# ELC102_-_Score_Board_-_Red_Digits.net
KiCad netlist of a schematic drawn in Altium Designer
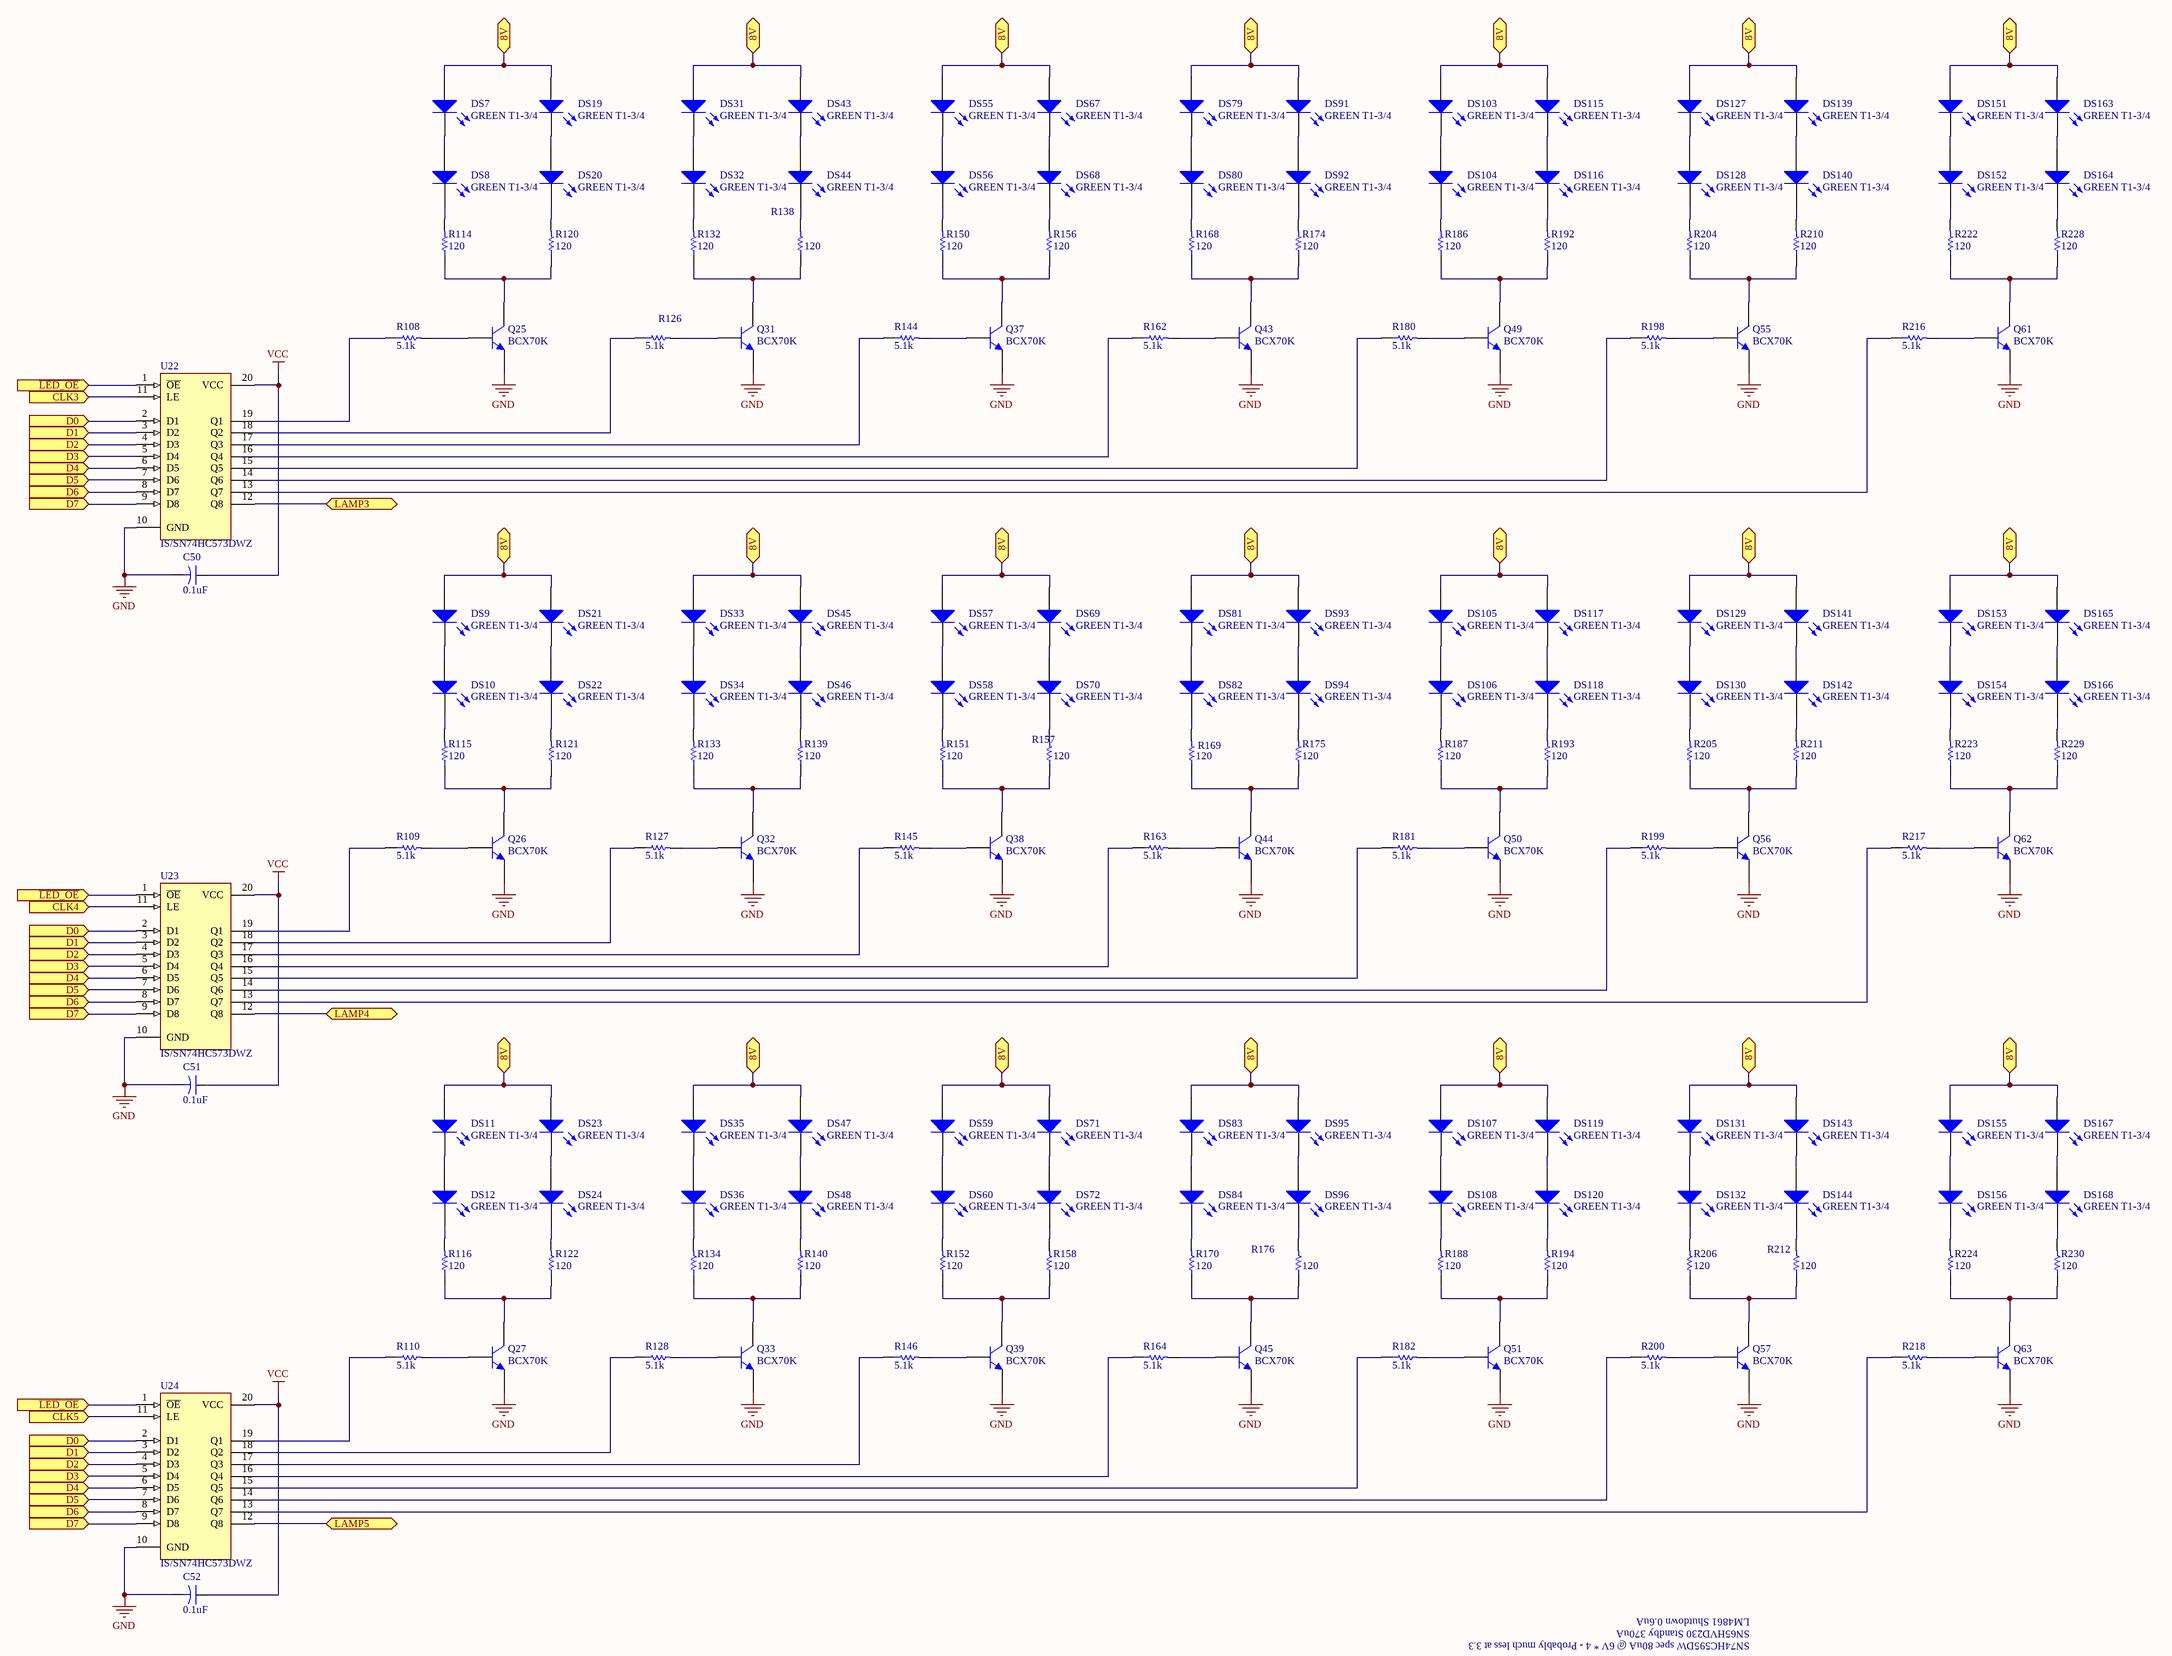
[diagram p0: ELC102 - Score Board - Red Digits.SchDoc]

(export (version "E")
  (design (tool "Eeschema 10.0.6"))
  (components
    (comp (ref "C50")
      (value "0.1uF")
      (footprint "C0805")
      (description "Kemet .1uF 0805")
      (fields
        (field (name "MANUFACTURER") "Kemet")
        (field (name "MANUFACTURER PART NUMBER") "C0805C104K5RACTU")
        (field (name "SOURCE") "Digikey")
      )
      (libsource (lib "ScoreBoard") (part "CS/C0805C104K5RACK"))
    )
    (comp (ref "C51")
      (value "0.1uF")
      (footprint "C0805")
      (description "Kemet .1uF 0805")
      (fields
        (field (name "MANUFACTURER") "Kemet")
        (field (name "MANUFACTURER PART NUMBER") "C0805C104K5RACTU")
        (field (name "SOURCE") "Digikey")
      )
      (libsource (lib "ScoreBoard") (part "CS/C0805C104K5RACK"))
    )
    (comp (ref "C52")
      (value "0.1uF")
      (footprint "C0805")
      (description "Kemet .1uF 0805")
      (fields
        (field (name "MANUFACTURER") "Kemet")
        (field (name "MANUFACTURER PART NUMBER") "C0805C104K5RACTU")
        (field (name "SOURCE") "Digikey")
      )
      (libsource (lib "ScoreBoard") (part "CS/C0805C104K5RACK"))
    )
    (comp (ref "DS7")
      (value "GREEN T1-3/4")
      (footprint "LED T1-3/4 Flush")
      (description "Optek LED Green/Clear High Brightness T1-3/4")
      (fields
        (field (name "MANUFACTURER") "OPTEK")
        (field (name "MANUFACTURER PART NUMBER") "OVLFG3C7")
        (field (name "SOURCE") "Digikey")
      )
      (libsource (lib "ScoreBoard") (part "LGCOVLFG3C7Z"))
    )
    (comp (ref "DS8")
      (value "GREEN T1-3/4")
      (footprint "LED T1-3/4 Flush")
      (description "Optek LED Green/Clear High Brightness T1-3/4")
      (fields
        (field (name "MANUFACTURER") "OPTEK")
        (field (name "MANUFACTURER PART NUMBER") "OVLFG3C7")
        (field (name "SOURCE") "Digikey")
      )
      (libsource (lib "ScoreBoard") (part "LGCOVLFG3C7Z"))
    )
    (comp (ref "DS9")
      (value "GREEN T1-3/4")
      (footprint "LED T1-3/4 Flush")
      (description "Optek LED Green/Clear High Brightness T1-3/4")
      (fields
        (field (name "MANUFACTURER") "OPTEK")
        (field (name "MANUFACTURER PART NUMBER") "OVLFG3C7")
        (field (name "SOURCE") "Digikey")
      )
      (libsource (lib "ScoreBoard") (part "LGCOVLFG3C7Z"))
    )
    (comp (ref "DS10")
      (value "GREEN T1-3/4")
      (footprint "LED T1-3/4 Flush")
      (description "Optek LED Green/Clear High Brightness T1-3/4")
      (fields
        (field (name "MANUFACTURER") "OPTEK")
        (field (name "MANUFACTURER PART NUMBER") "OVLFG3C7")
        (field (name "SOURCE") "Digikey")
      )
      (libsource (lib "ScoreBoard") (part "LGCOVLFG3C7Z"))
    )
    (comp (ref "DS11")
      (value "GREEN T1-3/4")
      (footprint "LED T1-3/4 Flush")
      (description "Optek LED Green/Clear High Brightness T1-3/4")
      (fields
        (field (name "MANUFACTURER") "OPTEK")
        (field (name "MANUFACTURER PART NUMBER") "OVLFG3C7")
        (field (name "SOURCE") "Digikey")
      )
      (libsource (lib "ScoreBoard") (part "LGCOVLFG3C7Z"))
    )
    (comp (ref "DS12")
      (value "GREEN T1-3/4")
      (footprint "LED T1-3/4 Flush")
      (description "Optek LED Green/Clear High Brightness T1-3/4")
      (fields
        (field (name "MANUFACTURER") "OPTEK")
        (field (name "MANUFACTURER PART NUMBER") "OVLFG3C7")
        (field (name "SOURCE") "Digikey")
      )
      (libsource (lib "ScoreBoard") (part "LGCOVLFG3C7Z"))
    )
    (comp (ref "DS19")
      (value "GREEN T1-3/4")
      (footprint "LED T1-3/4 Flush")
      (description "Optek LED Green/Clear High Brightness T1-3/4")
      (fields
        (field (name "MANUFACTURER") "OPTEK")
        (field (name "MANUFACTURER PART NUMBER") "OVLFG3C7")
        (field (name "SOURCE") "Digikey")
      )
      (libsource (lib "ScoreBoard") (part "LGCOVLFG3C7Z"))
    )
    (comp (ref "DS20")
      (value "GREEN T1-3/4")
      (footprint "LED T1-3/4 Flush")
      (description "Optek LED Green/Clear High Brightness T1-3/4")
      (fields
        (field (name "MANUFACTURER") "OPTEK")
        (field (name "MANUFACTURER PART NUMBER") "OVLFG3C7")
        (field (name "SOURCE") "Digikey")
      )
      (libsource (lib "ScoreBoard") (part "LGCOVLFG3C7Z"))
    )
    (comp (ref "DS21")
      (value "GREEN T1-3/4")
      (footprint "LED T1-3/4 Flush")
      (description "Optek LED Green/Clear High Brightness T1-3/4")
      (fields
        (field (name "MANUFACTURER") "OPTEK")
        (field (name "MANUFACTURER PART NUMBER") "OVLFG3C7")
        (field (name "SOURCE") "Digikey")
      )
      (libsource (lib "ScoreBoard") (part "LGCOVLFG3C7Z"))
    )
    (comp (ref "DS22")
      (value "GREEN T1-3/4")
      (footprint "LED T1-3/4 Flush")
      (description "Optek LED Green/Clear High Brightness T1-3/4")
      (fields
        (field (name "MANUFACTURER") "OPTEK")
        (field (name "MANUFACTURER PART NUMBER") "OVLFG3C7")
        (field (name "SOURCE") "Digikey")
      )
      (libsource (lib "ScoreBoard") (part "LGCOVLFG3C7Z"))
    )
    (comp (ref "DS23")
      (value "GREEN T1-3/4")
      (footprint "LED T1-3/4 Flush")
      (description "Optek LED Green/Clear High Brightness T1-3/4")
      (fields
        (field (name "MANUFACTURER") "OPTEK")
        (field (name "MANUFACTURER PART NUMBER") "OVLFG3C7")
        (field (name "SOURCE") "Digikey")
      )
      (libsource (lib "ScoreBoard") (part "LGCOVLFG3C7Z"))
    )
    (comp (ref "DS24")
      (value "GREEN T1-3/4")
      (footprint "LED T1-3/4 Flush")
      (description "Optek LED Green/Clear High Brightness T1-3/4")
      (fields
        (field (name "MANUFACTURER") "OPTEK")
        (field (name "MANUFACTURER PART NUMBER") "OVLFG3C7")
        (field (name "SOURCE") "Digikey")
      )
      (libsource (lib "ScoreBoard") (part "LGCOVLFG3C7Z"))
    )
    (comp (ref "DS31")
      (value "GREEN T1-3/4")
      (footprint "LED T1-3/4 Flush")
      (description "Optek LED Green/Clear High Brightness T1-3/4")
      (fields
        (field (name "MANUFACTURER") "OPTEK")
        (field (name "MANUFACTURER PART NUMBER") "OVLFG3C7")
        (field (name "SOURCE") "Digikey")
      )
      (libsource (lib "ScoreBoard") (part "LGCOVLFG3C7Z"))
    )
    (comp (ref "DS32")
      (value "GREEN T1-3/4")
      (footprint "LED T1-3/4 Flush")
      (description "Optek LED Green/Clear High Brightness T1-3/4")
      (fields
        (field (name "MANUFACTURER") "OPTEK")
        (field (name "MANUFACTURER PART NUMBER") "OVLFG3C7")
        (field (name "SOURCE") "Digikey")
      )
      (libsource (lib "ScoreBoard") (part "LGCOVLFG3C7Z"))
    )
    (comp (ref "DS33")
      (value "GREEN T1-3/4")
      (footprint "LED T1-3/4 Flush")
      (description "Optek LED Green/Clear High Brightness T1-3/4")
      (fields
        (field (name "MANUFACTURER") "OPTEK")
        (field (name "MANUFACTURER PART NUMBER") "OVLFG3C7")
        (field (name "SOURCE") "Digikey")
      )
      (libsource (lib "ScoreBoard") (part "LGCOVLFG3C7Z"))
    )
    (comp (ref "DS34")
      (value "GREEN T1-3/4")
      (footprint "LED T1-3/4 Flush")
      (description "Optek LED Green/Clear High Brightness T1-3/4")
      (fields
        (field (name "MANUFACTURER") "OPTEK")
        (field (name "MANUFACTURER PART NUMBER") "OVLFG3C7")
        (field (name "SOURCE") "Digikey")
      )
      (libsource (lib "ScoreBoard") (part "LGCOVLFG3C7Z"))
    )
    (comp (ref "DS35")
      (value "GREEN T1-3/4")
      (footprint "LED T1-3/4 Flush")
      (description "Optek LED Green/Clear High Brightness T1-3/4")
      (fields
        (field (name "MANUFACTURER") "OPTEK")
        (field (name "MANUFACTURER PART NUMBER") "OVLFG3C7")
        (field (name "SOURCE") "Digikey")
      )
      (libsource (lib "ScoreBoard") (part "LGCOVLFG3C7Z"))
    )
    (comp (ref "DS36")
      (value "GREEN T1-3/4")
      (footprint "LED T1-3/4 Flush")
      (description "Optek LED Green/Clear High Brightness T1-3/4")
      (fields
        (field (name "MANUFACTURER") "OPTEK")
        (field (name "MANUFACTURER PART NUMBER") "OVLFG3C7")
        (field (name "SOURCE") "Digikey")
      )
      (libsource (lib "ScoreBoard") (part "LGCOVLFG3C7Z"))
    )
    (comp (ref "DS43")
      (value "GREEN T1-3/4")
      (footprint "LED T1-3/4 Flush")
      (description "Optek LED Green/Clear High Brightness T1-3/4")
      (fields
        (field (name "MANUFACTURER") "OPTEK")
        (field (name "MANUFACTURER PART NUMBER") "OVLFG3C7")
        (field (name "SOURCE") "Digikey")
      )
      (libsource (lib "ScoreBoard") (part "LGCOVLFG3C7Z"))
    )
    (comp (ref "DS44")
      (value "GREEN T1-3/4")
      (footprint "LED T1-3/4 Flush")
      (description "Optek LED Green/Clear High Brightness T1-3/4")
      (fields
        (field (name "MANUFACTURER") "OPTEK")
        (field (name "MANUFACTURER PART NUMBER") "OVLFG3C7")
        (field (name "SOURCE") "Digikey")
      )
      (libsource (lib "ScoreBoard") (part "LGCOVLFG3C7Z"))
    )
    (comp (ref "DS45")
      (value "GREEN T1-3/4")
      (footprint "LED T1-3/4 Flush")
      (description "Optek LED Green/Clear High Brightness T1-3/4")
      (fields
        (field (name "MANUFACTURER") "OPTEK")
        (field (name "MANUFACTURER PART NUMBER") "OVLFG3C7")
        (field (name "SOURCE") "Digikey")
      )
      (libsource (lib "ScoreBoard") (part "LGCOVLFG3C7Z"))
    )
    (comp (ref "DS46")
      (value "GREEN T1-3/4")
      (footprint "LED T1-3/4 Flush")
      (description "Optek LED Green/Clear High Brightness T1-3/4")
      (fields
        (field (name "MANUFACTURER") "OPTEK")
        (field (name "MANUFACTURER PART NUMBER") "OVLFG3C7")
        (field (name "SOURCE") "Digikey")
      )
      (libsource (lib "ScoreBoard") (part "LGCOVLFG3C7Z"))
    )
    (comp (ref "DS47")
      (value "GREEN T1-3/4")
      (footprint "LED T1-3/4 Flush")
      (description "Optek LED Green/Clear High Brightness T1-3/4")
      (fields
        (field (name "MANUFACTURER") "OPTEK")
        (field (name "MANUFACTURER PART NUMBER") "OVLFG3C7")
        (field (name "SOURCE") "Digikey")
      )
      (libsource (lib "ScoreBoard") (part "LGCOVLFG3C7Z"))
    )
    (comp (ref "DS48")
      (value "GREEN T1-3/4")
      (footprint "LED T1-3/4 Flush")
      (description "Optek LED Green/Clear High Brightness T1-3/4")
      (fields
        (field (name "MANUFACTURER") "OPTEK")
        (field (name "MANUFACTURER PART NUMBER") "OVLFG3C7")
        (field (name "SOURCE") "Digikey")
      )
      (libsource (lib "ScoreBoard") (part "LGCOVLFG3C7Z"))
    )
    (comp (ref "DS55")
      (value "GREEN T1-3/4")
      (footprint "LED T1-3/4 Flush")
      (description "Optek LED Green/Clear High Brightness T1-3/4")
      (fields
        (field (name "MANUFACTURER") "OPTEK")
        (field (name "MANUFACTURER PART NUMBER") "OVLFG3C7")
        (field (name "SOURCE") "Digikey")
      )
      (libsource (lib "ScoreBoard") (part "LGCOVLFG3C7Z"))
    )
    (comp (ref "DS56")
      (value "GREEN T1-3/4")
      (footprint "LED T1-3/4 Flush")
      (description "Optek LED Green/Clear High Brightness T1-3/4")
      (fields
        (field (name "MANUFACTURER") "OPTEK")
        (field (name "MANUFACTURER PART NUMBER") "OVLFG3C7")
        (field (name "SOURCE") "Digikey")
      )
      (libsource (lib "ScoreBoard") (part "LGCOVLFG3C7Z"))
    )
    (comp (ref "DS57")
      (value "GREEN T1-3/4")
      (footprint "LED T1-3/4 Flush")
      (description "Optek LED Green/Clear High Brightness T1-3/4")
      (fields
        (field (name "MANUFACTURER") "OPTEK")
        (field (name "MANUFACTURER PART NUMBER") "OVLFG3C7")
        (field (name "SOURCE") "Digikey")
      )
      (libsource (lib "ScoreBoard") (part "LGCOVLFG3C7Z"))
    )
    (comp (ref "DS58")
      (value "GREEN T1-3/4")
      (footprint "LED T1-3/4 Flush")
      (description "Optek LED Green/Clear High Brightness T1-3/4")
      (fields
        (field (name "MANUFACTURER") "OPTEK")
        (field (name "MANUFACTURER PART NUMBER") "OVLFG3C7")
        (field (name "SOURCE") "Digikey")
      )
      (libsource (lib "ScoreBoard") (part "LGCOVLFG3C7Z"))
    )
    (comp (ref "DS59")
      (value "GREEN T1-3/4")
      (footprint "LED T1-3/4 Flush")
      (description "Optek LED Green/Clear High Brightness T1-3/4")
      (fields
        (field (name "MANUFACTURER") "OPTEK")
        (field (name "MANUFACTURER PART NUMBER") "OVLFG3C7")
        (field (name "SOURCE") "Digikey")
      )
      (libsource (lib "ScoreBoard") (part "LGCOVLFG3C7Z"))
    )
    (comp (ref "DS60")
      (value "GREEN T1-3/4")
      (footprint "LED T1-3/4 Flush")
      (description "Optek LED Green/Clear High Brightness T1-3/4")
      (fields
        (field (name "MANUFACTURER") "OPTEK")
        (field (name "MANUFACTURER PART NUMBER") "OVLFG3C7")
        (field (name "SOURCE") "Digikey")
      )
      (libsource (lib "ScoreBoard") (part "LGCOVLFG3C7Z"))
    )
    (comp (ref "DS67")
      (value "GREEN T1-3/4")
      (footprint "LED T1-3/4 Flush")
      (description "Optek LED Green/Clear High Brightness T1-3/4")
      (fields
        (field (name "MANUFACTURER") "OPTEK")
        (field (name "MANUFACTURER PART NUMBER") "OVLFG3C7")
        (field (name "SOURCE") "Digikey")
      )
      (libsource (lib "ScoreBoard") (part "LGCOVLFG3C7Z"))
    )
    (comp (ref "DS68")
      (value "GREEN T1-3/4")
      (footprint "LED T1-3/4 Flush")
      (description "Optek LED Green/Clear High Brightness T1-3/4")
      (fields
        (field (name "MANUFACTURER") "OPTEK")
        (field (name "MANUFACTURER PART NUMBER") "OVLFG3C7")
        (field (name "SOURCE") "Digikey")
      )
      (libsource (lib "ScoreBoard") (part "LGCOVLFG3C7Z"))
    )
    (comp (ref "DS69")
      (value "GREEN T1-3/4")
      (footprint "LED T1-3/4 Flush")
      (description "Optek LED Green/Clear High Brightness T1-3/4")
      (fields
        (field (name "MANUFACTURER") "OPTEK")
        (field (name "MANUFACTURER PART NUMBER") "OVLFG3C7")
        (field (name "SOURCE") "Digikey")
      )
      (libsource (lib "ScoreBoard") (part "LGCOVLFG3C7Z"))
    )
    (comp (ref "DS70")
      (value "GREEN T1-3/4")
      (footprint "LED T1-3/4 Flush")
      (description "Optek LED Green/Clear High Brightness T1-3/4")
      (fields
        (field (name "MANUFACTURER") "OPTEK")
        (field (name "MANUFACTURER PART NUMBER") "OVLFG3C7")
        (field (name "SOURCE") "Digikey")
      )
      (libsource (lib "ScoreBoard") (part "LGCOVLFG3C7Z"))
    )
    (comp (ref "DS71")
      (value "GREEN T1-3/4")
      (footprint "LED T1-3/4 Flush")
      (description "Optek LED Green/Clear High Brightness T1-3/4")
      (fields
        (field (name "MANUFACTURER") "OPTEK")
        (field (name "MANUFACTURER PART NUMBER") "OVLFG3C7")
        (field (name "SOURCE") "Digikey")
      )
      (libsource (lib "ScoreBoard") (part "LGCOVLFG3C7Z"))
    )
    (comp (ref "DS72")
      (value "GREEN T1-3/4")
      (footprint "LED T1-3/4 Flush")
      (description "Optek LED Green/Clear High Brightness T1-3/4")
      (fields
        (field (name "MANUFACTURER") "OPTEK")
        (field (name "MANUFACTURER PART NUMBER") "OVLFG3C7")
        (field (name "SOURCE") "Digikey")
      )
      (libsource (lib "ScoreBoard") (part "LGCOVLFG3C7Z"))
    )
    (comp (ref "DS79")
      (value "GREEN T1-3/4")
      (footprint "LED T1-3/4 Flush")
      (description "Optek LED Green/Clear High Brightness T1-3/4")
      (fields
        (field (name "MANUFACTURER") "OPTEK")
        (field (name "MANUFACTURER PART NUMBER") "OVLFG3C7")
        (field (name "SOURCE") "Digikey")
      )
      (libsource (lib "ScoreBoard") (part "LGCOVLFG3C7Z"))
    )
    (comp (ref "DS80")
      (value "GREEN T1-3/4")
      (footprint "LED T1-3/4 Flush")
      (description "Optek LED Green/Clear High Brightness T1-3/4")
      (fields
        (field (name "MANUFACTURER") "OPTEK")
        (field (name "MANUFACTURER PART NUMBER") "OVLFG3C7")
        (field (name "SOURCE") "Digikey")
      )
      (libsource (lib "ScoreBoard") (part "LGCOVLFG3C7Z"))
    )
    (comp (ref "DS81")
      (value "GREEN T1-3/4")
      (footprint "LED T1-3/4 Flush")
      (description "Optek LED Green/Clear High Brightness T1-3/4")
      (fields
        (field (name "MANUFACTURER") "OPTEK")
        (field (name "MANUFACTURER PART NUMBER") "OVLFG3C7")
        (field (name "SOURCE") "Digikey")
      )
      (libsource (lib "ScoreBoard") (part "LGCOVLFG3C7Z"))
    )
    (comp (ref "DS82")
      (value "GREEN T1-3/4")
      (footprint "LED T1-3/4 Flush")
      (description "Optek LED Green/Clear High Brightness T1-3/4")
      (fields
        (field (name "MANUFACTURER") "OPTEK")
        (field (name "MANUFACTURER PART NUMBER") "OVLFG3C7")
        (field (name "SOURCE") "Digikey")
      )
      (libsource (lib "ScoreBoard") (part "LGCOVLFG3C7Z"))
    )
    (comp (ref "DS83")
      (value "GREEN T1-3/4")
      (footprint "LED T1-3/4 Flush")
      (description "Optek LED Green/Clear High Brightness T1-3/4")
      (fields
        (field (name "MANUFACTURER") "OPTEK")
        (field (name "MANUFACTURER PART NUMBER") "OVLFG3C7")
        (field (name "SOURCE") "Digikey")
      )
      (libsource (lib "ScoreBoard") (part "LGCOVLFG3C7Z"))
    )
    (comp (ref "DS84")
      (value "GREEN T1-3/4")
      (footprint "LED T1-3/4 Flush")
      (description "Optek LED Green/Clear High Brightness T1-3/4")
      (fields
        (field (name "MANUFACTURER") "OPTEK")
        (field (name "MANUFACTURER PART NUMBER") "OVLFG3C7")
        (field (name "SOURCE") "Digikey")
      )
      (libsource (lib "ScoreBoard") (part "LGCOVLFG3C7Z"))
    )
    (comp (ref "DS91")
      (value "GREEN T1-3/4")
      (footprint "LED T1-3/4 Flush")
      (description "Optek LED Green/Clear High Brightness T1-3/4")
      (fields
        (field (name "MANUFACTURER") "OPTEK")
        (field (name "MANUFACTURER PART NUMBER") "OVLFG3C7")
        (field (name "SOURCE") "Digikey")
      )
      (libsource (lib "ScoreBoard") (part "LGCOVLFG3C7Z"))
    )
    (comp (ref "DS92")
      (value "GREEN T1-3/4")
      (footprint "LED T1-3/4 Flush")
      (description "Optek LED Green/Clear High Brightness T1-3/4")
      (fields
        (field (name "MANUFACTURER") "OPTEK")
        (field (name "MANUFACTURER PART NUMBER") "OVLFG3C7")
        (field (name "SOURCE") "Digikey")
      )
      (libsource (lib "ScoreBoard") (part "LGCOVLFG3C7Z"))
    )
    (comp (ref "DS93")
      (value "GREEN T1-3/4")
      (footprint "LED T1-3/4 Flush")
      (description "Optek LED Green/Clear High Brightness T1-3/4")
      (fields
        (field (name "MANUFACTURER") "OPTEK")
        (field (name "MANUFACTURER PART NUMBER") "OVLFG3C7")
        (field (name "SOURCE") "Digikey")
      )
      (libsource (lib "ScoreBoard") (part "LGCOVLFG3C7Z"))
    )
    (comp (ref "DS94")
      (value "GREEN T1-3/4")
      (footprint "LED T1-3/4 Flush")
      (description "Optek LED Green/Clear High Brightness T1-3/4")
      (fields
        (field (name "MANUFACTURER") "OPTEK")
        (field (name "MANUFACTURER PART NUMBER") "OVLFG3C7")
        (field (name "SOURCE") "Digikey")
      )
      (libsource (lib "ScoreBoard") (part "LGCOVLFG3C7Z"))
    )
    (comp (ref "DS95")
      (value "GREEN T1-3/4")
      (footprint "LED T1-3/4 Flush")
      (description "Optek LED Green/Clear High Brightness T1-3/4")
      (fields
        (field (name "MANUFACTURER") "OPTEK")
        (field (name "MANUFACTURER PART NUMBER") "OVLFG3C7")
        (field (name "SOURCE") "Digikey")
      )
      (libsource (lib "ScoreBoard") (part "LGCOVLFG3C7Z"))
    )
    (comp (ref "DS96")
      (value "GREEN T1-3/4")
      (footprint "LED T1-3/4 Flush")
      (description "Optek LED Green/Clear High Brightness T1-3/4")
      (fields
        (field (name "MANUFACTURER") "OPTEK")
        (field (name "MANUFACTURER PART NUMBER") "OVLFG3C7")
        (field (name "SOURCE") "Digikey")
      )
      (libsource (lib "ScoreBoard") (part "LGCOVLFG3C7Z"))
    )
    (comp (ref "DS103")
      (value "GREEN T1-3/4")
      (footprint "LED T1-3/4 Flush")
      (description "Optek LED Green/Clear High Brightness T1-3/4")
      (fields
        (field (name "MANUFACTURER") "OPTEK")
        (field (name "MANUFACTURER PART NUMBER") "OVLFG3C7")
        (field (name "SOURCE") "Digikey")
      )
      (libsource (lib "ScoreBoard") (part "LGCOVLFG3C7Z"))
    )
    (comp (ref "DS104")
      (value "GREEN T1-3/4")
      (footprint "LED T1-3/4 Flush")
      (description "Optek LED Green/Clear High Brightness T1-3/4")
      (fields
        (field (name "MANUFACTURER") "OPTEK")
        (field (name "MANUFACTURER PART NUMBER") "OVLFG3C7")
        (field (name "SOURCE") "Digikey")
      )
      (libsource (lib "ScoreBoard") (part "LGCOVLFG3C7Z"))
    )
    (comp (ref "DS105")
      (value "GREEN T1-3/4")
      (footprint "LED T1-3/4 Flush")
      (description "Optek LED Green/Clear High Brightness T1-3/4")
      (fields
        (field (name "MANUFACTURER") "OPTEK")
        (field (name "MANUFACTURER PART NUMBER") "OVLFG3C7")
        (field (name "SOURCE") "Digikey")
      )
      (libsource (lib "ScoreBoard") (part "LGCOVLFG3C7Z"))
    )
    (comp (ref "DS106")
      (value "GREEN T1-3/4")
      (footprint "LED T1-3/4 Flush")
      (description "Optek LED Green/Clear High Brightness T1-3/4")
      (fields
        (field (name "MANUFACTURER") "OPTEK")
        (field (name "MANUFACTURER PART NUMBER") "OVLFG3C7")
        (field (name "SOURCE") "Digikey")
      )
      (libsource (lib "ScoreBoard") (part "LGCOVLFG3C7Z"))
    )
    (comp (ref "DS107")
      (value "GREEN T1-3/4")
      (footprint "LED T1-3/4 Flush")
      (description "Optek LED Green/Clear High Brightness T1-3/4")
      (fields
        (field (name "MANUFACTURER") "OPTEK")
        (field (name "MANUFACTURER PART NUMBER") "OVLFG3C7")
        (field (name "SOURCE") "Digikey")
      )
      (libsource (lib "ScoreBoard") (part "LGCOVLFG3C7Z"))
    )
    (comp (ref "DS108")
      (value "GREEN T1-3/4")
      (footprint "LED T1-3/4 Flush")
      (description "Optek LED Green/Clear High Brightness T1-3/4")
      (fields
        (field (name "MANUFACTURER") "OPTEK")
        (field (name "MANUFACTURER PART NUMBER") "OVLFG3C7")
        (field (name "SOURCE") "Digikey")
      )
      (libsource (lib "ScoreBoard") (part "LGCOVLFG3C7Z"))
    )
    (comp (ref "DS115")
      (value "GREEN T1-3/4")
      (footprint "LED T1-3/4 Flush")
      (description "Optek LED Green/Clear High Brightness T1-3/4")
      (fields
        (field (name "MANUFACTURER") "OPTEK")
        (field (name "MANUFACTURER PART NUMBER") "OVLFG3C7")
        (field (name "SOURCE") "Digikey")
      )
      (libsource (lib "ScoreBoard") (part "LGCOVLFG3C7Z"))
    )
    (comp (ref "DS116")
      (value "GREEN T1-3/4")
      (footprint "LED T1-3/4 Flush")
      (description "Optek LED Green/Clear High Brightness T1-3/4")
      (fields
        (field (name "MANUFACTURER") "OPTEK")
        (field (name "MANUFACTURER PART NUMBER") "OVLFG3C7")
        (field (name "SOURCE") "Digikey")
      )
      (libsource (lib "ScoreBoard") (part "LGCOVLFG3C7Z"))
    )
    (comp (ref "DS117")
      (value "GREEN T1-3/4")
      (footprint "LED T1-3/4 Flush")
      (description "Optek LED Green/Clear High Brightness T1-3/4")
      (fields
        (field (name "MANUFACTURER") "OPTEK")
        (field (name "MANUFACTURER PART NUMBER") "OVLFG3C7")
        (field (name "SOURCE") "Digikey")
      )
      (libsource (lib "ScoreBoard") (part "LGCOVLFG3C7Z"))
    )
    (comp (ref "DS118")
      (value "GREEN T1-3/4")
      (footprint "LED T1-3/4 Flush")
      (description "Optek LED Green/Clear High Brightness T1-3/4")
      (fields
        (field (name "MANUFACTURER") "OPTEK")
        (field (name "MANUFACTURER PART NUMBER") "OVLFG3C7")
        (field (name "SOURCE") "Digikey")
      )
      (libsource (lib "ScoreBoard") (part "LGCOVLFG3C7Z"))
    )
    (comp (ref "DS119")
      (value "GREEN T1-3/4")
      (footprint "LED T1-3/4 Flush")
      (description "Optek LED Green/Clear High Brightness T1-3/4")
      (fields
        (field (name "MANUFACTURER") "OPTEK")
        (field (name "MANUFACTURER PART NUMBER") "OVLFG3C7")
        (field (name "SOURCE") "Digikey")
      )
      (libsource (lib "ScoreBoard") (part "LGCOVLFG3C7Z"))
    )
    (comp (ref "DS120")
      (value "GREEN T1-3/4")
      (footprint "LED T1-3/4 Flush")
      (description "Optek LED Green/Clear High Brightness T1-3/4")
      (fields
        (field (name "MANUFACTURER") "OPTEK")
        (field (name "MANUFACTURER PART NUMBER") "OVLFG3C7")
        (field (name "SOURCE") "Digikey")
      )
      (libsource (lib "ScoreBoard") (part "LGCOVLFG3C7Z"))
    )
    (comp (ref "DS127")
      (value "GREEN T1-3/4")
      (footprint "LED T1-3/4 Flush")
      (description "Optek LED Green/Clear High Brightness T1-3/4")
      (fields
        (field (name "MANUFACTURER") "OPTEK")
        (field (name "MANUFACTURER PART NUMBER") "OVLFG3C7")
        (field (name "SOURCE") "Digikey")
      )
      (libsource (lib "ScoreBoard") (part "LGCOVLFG3C7Z"))
    )
    (comp (ref "DS128")
      (value "GREEN T1-3/4")
      (footprint "LED T1-3/4 Flush")
      (description "Optek LED Green/Clear High Brightness T1-3/4")
      (fields
        (field (name "MANUFACTURER") "OPTEK")
        (field (name "MANUFACTURER PART NUMBER") "OVLFG3C7")
        (field (name "SOURCE") "Digikey")
      )
      (libsource (lib "ScoreBoard") (part "LGCOVLFG3C7Z"))
    )
    (comp (ref "DS129")
      (value "GREEN T1-3/4")
      (footprint "LED T1-3/4 Flush")
      (description "Optek LED Green/Clear High Brightness T1-3/4")
      (fields
        (field (name "MANUFACTURER") "OPTEK")
        (field (name "MANUFACTURER PART NUMBER") "OVLFG3C7")
        (field (name "SOURCE") "Digikey")
      )
      (libsource (lib "ScoreBoard") (part "LGCOVLFG3C7Z"))
    )
    (comp (ref "DS130")
      (value "GREEN T1-3/4")
      (footprint "LED T1-3/4 Flush")
      (description "Optek LED Green/Clear High Brightness T1-3/4")
      (fields
        (field (name "MANUFACTURER") "OPTEK")
        (field (name "MANUFACTURER PART NUMBER") "OVLFG3C7")
        (field (name "SOURCE") "Digikey")
      )
      (libsource (lib "ScoreBoard") (part "LGCOVLFG3C7Z"))
    )
    (comp (ref "DS131")
      (value "GREEN T1-3/4")
      (footprint "LED T1-3/4 Flush")
      (description "Optek LED Green/Clear High Brightness T1-3/4")
      (fields
        (field (name "MANUFACTURER") "OPTEK")
        (field (name "MANUFACTURER PART NUMBER") "OVLFG3C7")
        (field (name "SOURCE") "Digikey")
      )
      (libsource (lib "ScoreBoard") (part "LGCOVLFG3C7Z"))
    )
    (comp (ref "DS132")
      (value "GREEN T1-3/4")
      (footprint "LED T1-3/4 Flush")
      (description "Optek LED Green/Clear High Brightness T1-3/4")
      (fields
        (field (name "MANUFACTURER") "OPTEK")
        (field (name "MANUFACTURER PART NUMBER") "OVLFG3C7")
        (field (name "SOURCE") "Digikey")
      )
      (libsource (lib "ScoreBoard") (part "LGCOVLFG3C7Z"))
    )
    (comp (ref "DS139")
      (value "GREEN T1-3/4")
      (footprint "LED T1-3/4 Flush")
      (description "Optek LED Green/Clear High Brightness T1-3/4")
      (fields
        (field (name "MANUFACTURER") "OPTEK")
        (field (name "MANUFACTURER PART NUMBER") "OVLFG3C7")
        (field (name "SOURCE") "Digikey")
      )
      (libsource (lib "ScoreBoard") (part "LGCOVLFG3C7Z"))
    )
    (comp (ref "DS140")
      (value "GREEN T1-3/4")
      (footprint "LED T1-3/4 Flush")
      (description "Optek LED Green/Clear High Brightness T1-3/4")
      (fields
        (field (name "MANUFACTURER") "OPTEK")
        (field (name "MANUFACTURER PART NUMBER") "OVLFG3C7")
        (field (name "SOURCE") "Digikey")
      )
      (libsource (lib "ScoreBoard") (part "LGCOVLFG3C7Z"))
    )
    (comp (ref "DS141")
      (value "GREEN T1-3/4")
      (footprint "LED T1-3/4 Flush")
      (description "Optek LED Green/Clear High Brightness T1-3/4")
      (fields
        (field (name "MANUFACTURER") "OPTEK")
        (field (name "MANUFACTURER PART NUMBER") "OVLFG3C7")
        (field (name "SOURCE") "Digikey")
      )
      (libsource (lib "ScoreBoard") (part "LGCOVLFG3C7Z"))
    )
    (comp (ref "DS142")
      (value "GREEN T1-3/4")
      (footprint "LED T1-3/4 Flush")
      (description "Optek LED Green/Clear High Brightness T1-3/4")
      (fields
        (field (name "MANUFACTURER") "OPTEK")
        (field (name "MANUFACTURER PART NUMBER") "OVLFG3C7")
        (field (name "SOURCE") "Digikey")
      )
      (libsource (lib "ScoreBoard") (part "LGCOVLFG3C7Z"))
    )
    (comp (ref "DS143")
      (value "GREEN T1-3/4")
      (footprint "LED T1-3/4 Flush")
      (description "Optek LED Green/Clear High Brightness T1-3/4")
      (fields
        (field (name "MANUFACTURER") "OPTEK")
        (field (name "MANUFACTURER PART NUMBER") "OVLFG3C7")
        (field (name "SOURCE") "Digikey")
      )
      (libsource (lib "ScoreBoard") (part "LGCOVLFG3C7Z"))
    )
    (comp (ref "DS144")
      (value "GREEN T1-3/4")
      (footprint "LED T1-3/4 Flush")
      (description "Optek LED Green/Clear High Brightness T1-3/4")
      (fields
        (field (name "MANUFACTURER") "OPTEK")
        (field (name "MANUFACTURER PART NUMBER") "OVLFG3C7")
        (field (name "SOURCE") "Digikey")
      )
      (libsource (lib "ScoreBoard") (part "LGCOVLFG3C7Z"))
    )
    (comp (ref "DS151")
      (value "GREEN T1-3/4")
      (footprint "LED T1-3/4 Flush")
      (description "Optek LED Green/Clear High Brightness T1-3/4")
      (fields
        (field (name "MANUFACTURER") "OPTEK")
        (field (name "MANUFACTURER PART NUMBER") "OVLFG3C7")
        (field (name "SOURCE") "Digikey")
      )
      (libsource (lib "ScoreBoard") (part "LGCOVLFG3C7Z"))
    )
    (comp (ref "DS152")
      (value "GREEN T1-3/4")
      (footprint "LED T1-3/4 Flush")
      (description "Optek LED Green/Clear High Brightness T1-3/4")
      (fields
        (field (name "MANUFACTURER") "OPTEK")
        (field (name "MANUFACTURER PART NUMBER") "OVLFG3C7")
        (field (name "SOURCE") "Digikey")
      )
      (libsource (lib "ScoreBoard") (part "LGCOVLFG3C7Z"))
    )
    (comp (ref "DS153")
      (value "GREEN T1-3/4")
      (footprint "LED T1-3/4 Flush")
      (description "Optek LED Green/Clear High Brightness T1-3/4")
      (fields
        (field (name "MANUFACTURER") "OPTEK")
        (field (name "MANUFACTURER PART NUMBER") "OVLFG3C7")
        (field (name "SOURCE") "Digikey")
      )
      (libsource (lib "ScoreBoard") (part "LGCOVLFG3C7Z"))
    )
    (comp (ref "DS154")
      (value "GREEN T1-3/4")
      (footprint "LED T1-3/4 Flush")
      (description "Optek LED Green/Clear High Brightness T1-3/4")
      (fields
        (field (name "MANUFACTURER") "OPTEK")
        (field (name "MANUFACTURER PART NUMBER") "OVLFG3C7")
        (field (name "SOURCE") "Digikey")
      )
      (libsource (lib "ScoreBoard") (part "LGCOVLFG3C7Z"))
    )
    (comp (ref "DS155")
      (value "GREEN T1-3/4")
      (footprint "LED T1-3/4 Flush")
      (description "Optek LED Green/Clear High Brightness T1-3/4")
      (fields
        (field (name "MANUFACTURER") "OPTEK")
        (field (name "MANUFACTURER PART NUMBER") "OVLFG3C7")
        (field (name "SOURCE") "Digikey")
      )
      (libsource (lib "ScoreBoard") (part "LGCOVLFG3C7Z"))
    )
    (comp (ref "DS156")
      (value "GREEN T1-3/4")
      (footprint "LED T1-3/4 Flush")
      (description "Optek LED Green/Clear High Brightness T1-3/4")
      (fields
        (field (name "MANUFACTURER") "OPTEK")
        (field (name "MANUFACTURER PART NUMBER") "OVLFG3C7")
        (field (name "SOURCE") "Digikey")
      )
      (libsource (lib "ScoreBoard") (part "LGCOVLFG3C7Z"))
    )
    (comp (ref "DS163")
      (value "GREEN T1-3/4")
      (footprint "LED T1-3/4 Flush")
      (description "Optek LED Green/Clear High Brightness T1-3/4")
      (fields
        (field (name "MANUFACTURER") "OPTEK")
        (field (name "MANUFACTURER PART NUMBER") "OVLFG3C7")
        (field (name "SOURCE") "Digikey")
      )
      (libsource (lib "ScoreBoard") (part "LGCOVLFG3C7Z"))
    )
    (comp (ref "DS164")
      (value "GREEN T1-3/4")
      (footprint "LED T1-3/4 Flush")
      (description "Optek LED Green/Clear High Brightness T1-3/4")
      (fields
        (field (name "MANUFACTURER") "OPTEK")
        (field (name "MANUFACTURER PART NUMBER") "OVLFG3C7")
        (field (name "SOURCE") "Digikey")
      )
      (libsource (lib "ScoreBoard") (part "LGCOVLFG3C7Z"))
    )
    (comp (ref "DS165")
      (value "GREEN T1-3/4")
      (footprint "LED T1-3/4 Flush")
      (description "Optek LED Green/Clear High Brightness T1-3/4")
      (fields
        (field (name "MANUFACTURER") "OPTEK")
        (field (name "MANUFACTURER PART NUMBER") "OVLFG3C7")
        (field (name "SOURCE") "Digikey")
      )
      (libsource (lib "ScoreBoard") (part "LGCOVLFG3C7Z"))
    )
    (comp (ref "DS166")
      (value "GREEN T1-3/4")
      (footprint "LED T1-3/4 Flush")
      (description "Optek LED Green/Clear High Brightness T1-3/4")
      (fields
        (field (name "MANUFACTURER") "OPTEK")
        (field (name "MANUFACTURER PART NUMBER") "OVLFG3C7")
        (field (name "SOURCE") "Digikey")
      )
      (libsource (lib "ScoreBoard") (part "LGCOVLFG3C7Z"))
    )
    (comp (ref "DS167")
      (value "GREEN T1-3/4")
      (footprint "LED T1-3/4 Flush")
      (description "Optek LED Green/Clear High Brightness T1-3/4")
      (fields
        (field (name "MANUFACTURER") "OPTEK")
        (field (name "MANUFACTURER PART NUMBER") "OVLFG3C7")
        (field (name "SOURCE") "Digikey")
      )
      (libsource (lib "ScoreBoard") (part "LGCOVLFG3C7Z"))
    )
    (comp (ref "DS168")
      (value "GREEN T1-3/4")
      (footprint "LED T1-3/4 Flush")
      (description "Optek LED Green/Clear High Brightness T1-3/4")
      (fields
        (field (name "MANUFACTURER") "OPTEK")
        (field (name "MANUFACTURER PART NUMBER") "OVLFG3C7")
        (field (name "SOURCE") "Digikey")
      )
      (libsource (lib "ScoreBoard") (part "LGCOVLFG3C7Z"))
    )
    (comp (ref "Q25")
      (value "BCX70K")
      (footprint "SOT23")
      (description "TRANS NPN AF 45V SOT-23")
      (fields (field (name "MANUFACTURER") "Fairchild Semiconductor") (field (name "SOURCE") "Digikey"))
      (libsource (lib "ScoreBoard") (part "QS/BCX70K00Z"))
    )
    (comp (ref "Q26")
      (value "BCX70K")
      (footprint "SOT23")
      (description "TRANS NPN AF 45V SOT-23")
      (fields (field (name "MANUFACTURER") "Fairchild Semiconductor") (field (name "SOURCE") "Digikey"))
      (libsource (lib "ScoreBoard") (part "QS/BCX70K00Z"))
    )
    (comp (ref "Q27")
      (value "BCX70K")
      (footprint "SOT23")
      (description "TRANS NPN AF 45V SOT-23")
      (fields (field (name "MANUFACTURER") "Fairchild Semiconductor") (field (name "SOURCE") "Digikey"))
      (libsource (lib "ScoreBoard") (part "QS/BCX70K00Z"))
    )
    (comp (ref "Q31")
      (value "BCX70K")
      (footprint "SOT23")
      (description "TRANS NPN AF 45V SOT-23")
      (fields (field (name "MANUFACTURER") "Fairchild Semiconductor") (field (name "SOURCE") "Digikey"))
      (libsource (lib "ScoreBoard") (part "QS/BCX70K00Z"))
    )
    (comp (ref "Q32")
      (value "BCX70K")
      (footprint "SOT23")
      (description "TRANS NPN AF 45V SOT-23")
      (fields (field (name "MANUFACTURER") "Fairchild Semiconductor") (field (name "SOURCE") "Digikey"))
      (libsource (lib "ScoreBoard") (part "QS/BCX70K00Z"))
    )
    (comp (ref "Q33")
      (value "BCX70K")
      (footprint "SOT23")
      (description "TRANS NPN AF 45V SOT-23")
      (fields (field (name "MANUFACTURER") "Fairchild Semiconductor") (field (name "SOURCE") "Digikey"))
      (libsource (lib "ScoreBoard") (part "QS/BCX70K00Z"))
    )
    (comp (ref "Q37")
      (value "BCX70K")
      (footprint "SOT23")
      (description "TRANS NPN AF 45V SOT-23")
      (fields (field (name "MANUFACTURER") "Fairchild Semiconductor") (field (name "SOURCE") "Digikey"))
      (libsource (lib "ScoreBoard") (part "QS/BCX70K00Z"))
    )
    (comp (ref "Q38")
      (value "BCX70K")
      (footprint "SOT23")
      (description "TRANS NPN AF 45V SOT-23")
      (fields (field (name "MANUFACTURER") "Fairchild Semiconductor") (field (name "SOURCE") "Digikey"))
      (libsource (lib "ScoreBoard") (part "QS/BCX70K00Z"))
    )
    (comp (ref "Q39")
      (value "BCX70K")
      (footprint "SOT23")
      (description "TRANS NPN AF 45V SOT-23")
      (fields (field (name "MANUFACTURER") "Fairchild Semiconductor") (field (name "SOURCE") "Digikey"))
      (libsource (lib "ScoreBoard") (part "QS/BCX70K00Z"))
    )
    (comp (ref "Q43")
      (value "BCX70K")
      (footprint "SOT23")
      (description "TRANS NPN AF 45V SOT-23")
      (fields (field (name "MANUFACTURER") "Fairchild Semiconductor") (field (name "SOURCE") "Digikey"))
      (libsource (lib "ScoreBoard") (part "QS/BCX70K00Z"))
    )
    (comp (ref "Q44")
      (value "BCX70K")
      (footprint "SOT23")
      (description "TRANS NPN AF 45V SOT-23")
      (fields (field (name "MANUFACTURER") "Fairchild Semiconductor") (field (name "SOURCE") "Digikey"))
      (libsource (lib "ScoreBoard") (part "QS/BCX70K00Z"))
    )
    (comp (ref "Q45")
      (value "BCX70K")
      (footprint "SOT23")
      (description "TRANS NPN AF 45V SOT-23")
      (fields (field (name "MANUFACTURER") "Fairchild Semiconductor") (field (name "SOURCE") "Digikey"))
      (libsource (lib "ScoreBoard") (part "QS/BCX70K00Z"))
    )
    (comp (ref "Q49")
      (value "BCX70K")
      (footprint "SOT23")
      (description "TRANS NPN AF 45V SOT-23")
      (fields (field (name "MANUFACTURER") "Fairchild Semiconductor") (field (name "SOURCE") "Digikey"))
      (libsource (lib "ScoreBoard") (part "QS/BCX70K00Z"))
    )
    (comp (ref "Q50")
      (value "BCX70K")
      (footprint "SOT23")
      (description "TRANS NPN AF 45V SOT-23")
      (fields (field (name "MANUFACTURER") "Fairchild Semiconductor") (field (name "SOURCE") "Digikey"))
      (libsource (lib "ScoreBoard") (part "QS/BCX70K00Z"))
    )
    (comp (ref "Q51")
      (value "BCX70K")
      (footprint "SOT23")
      (description "TRANS NPN AF 45V SOT-23")
      (fields (field (name "MANUFACTURER") "Fairchild Semiconductor") (field (name "SOURCE") "Digikey"))
      (libsource (lib "ScoreBoard") (part "QS/BCX70K00Z"))
    )
    (comp (ref "Q55")
      (value "BCX70K")
      (footprint "SOT23")
      (description "TRANS NPN AF 45V SOT-23")
      (fields (field (name "MANUFACTURER") "Fairchild Semiconductor") (field (name "SOURCE") "Digikey"))
      (libsource (lib "ScoreBoard") (part "QS/BCX70K00Z"))
    )
    (comp (ref "Q56")
      (value "BCX70K")
      (footprint "SOT23")
      (description "TRANS NPN AF 45V SOT-23")
      (fields (field (name "MANUFACTURER") "Fairchild Semiconductor") (field (name "SOURCE") "Digikey"))
      (libsource (lib "ScoreBoard") (part "QS/BCX70K00Z"))
    )
    (comp (ref "Q57")
      (value "BCX70K")
      (footprint "SOT23")
      (description "TRANS NPN AF 45V SOT-23")
      (fields (field (name "MANUFACTURER") "Fairchild Semiconductor") (field (name "SOURCE") "Digikey"))
      (libsource (lib "ScoreBoard") (part "QS/BCX70K00Z"))
    )
    (comp (ref "Q61")
      (value "BCX70K")
      (footprint "SOT23")
      (description "TRANS NPN AF 45V SOT-23")
      (fields (field (name "MANUFACTURER") "Fairchild Semiconductor") (field (name "SOURCE") "Digikey"))
      (libsource (lib "ScoreBoard") (part "QS/BCX70K00Z"))
    )
    (comp (ref "Q62")
      (value "BCX70K")
      (footprint "SOT23")
      (description "TRANS NPN AF 45V SOT-23")
      (fields (field (name "MANUFACTURER") "Fairchild Semiconductor") (field (name "SOURCE") "Digikey"))
      (libsource (lib "ScoreBoard") (part "QS/BCX70K00Z"))
    )
    (comp (ref "Q63")
      (value "BCX70K")
      (footprint "SOT23")
      (description "TRANS NPN AF 45V SOT-23")
      (fields (field (name "MANUFACTURER") "Fairchild Semiconductor") (field (name "SOURCE") "Digikey"))
      (libsource (lib "ScoreBoard") (part "QS/BCX70K00Z"))
    )
    (comp (ref "R108")
      (value "5.1k")
      (footprint "R0805")
      (description "RES 5.10K OHM 1/8W 1% 0805 SMD")
      (fields
        (field (name "MANUFACTURER") "Panasonic - ECG")
        (field (name "MANUFACTURER PART NUMBER") "ERJ-6ENF5101V")
      )
      (libsource (lib "eRCL") (part "ERJ-6ENF5101V"))
    )
    (comp (ref "R109")
      (value "5.1k")
      (footprint "R0805")
      (description "RES 5.10K OHM 1/8W 1% 0805 SMD")
      (fields
        (field (name "MANUFACTURER") "Panasonic - ECG")
        (field (name "MANUFACTURER PART NUMBER") "ERJ-6ENF5101V")
      )
      (libsource (lib "eRCL") (part "ERJ-6ENF5101V"))
    )
    (comp (ref "R110")
      (value "5.1k")
      (footprint "R0805")
      (description "RES 5.10K OHM 1/8W 1% 0805 SMD")
      (fields
        (field (name "MANUFACTURER") "Panasonic - ECG")
        (field (name "MANUFACTURER PART NUMBER") "ERJ-6ENF5101V")
      )
      (libsource (lib "eRCL") (part "ERJ-6ENF5101V"))
    )
    (comp (ref "R114")
      (value "120")
      (footprint "R1206")
      (description "RES 120 OHM 1/4W 1% 1206 SMD")
      (fields
        (field (name "MANUFACTURER") "Panasonic - ECG")
        (field (name "MANUFACTURER PART NUMBER") "ERJ-8ENF1200V")
      )
      (libsource (lib "eRCL") (part "ERJ-8ENF1200V"))
    )
    (comp (ref "R115")
      (value "120")
      (footprint "R1206")
      (description "RES 120 OHM 1/4W 1% 1206 SMD")
      (fields
        (field (name "MANUFACTURER") "Panasonic - ECG")
        (field (name "MANUFACTURER PART NUMBER") "ERJ-8ENF1200V")
      )
      (libsource (lib "eRCL") (part "ERJ-8ENF1200V"))
    )
    (comp (ref "R116")
      (value "120")
      (footprint "R1206")
      (description "RES 120 OHM 1/4W 1% 1206 SMD")
      (fields
        (field (name "MANUFACTURER") "Panasonic - ECG")
        (field (name "MANUFACTURER PART NUMBER") "ERJ-8ENF1200V")
      )
      (libsource (lib "eRCL") (part "ERJ-8ENF1200V"))
    )
    (comp (ref "R120")
      (value "120")
      (footprint "R1206")
      (description "RES 120 OHM 1/4W 1% 1206 SMD")
      (fields
        (field (name "MANUFACTURER") "Panasonic - ECG")
        (field (name "MANUFACTURER PART NUMBER") "ERJ-8ENF1200V")
      )
      (libsource (lib "eRCL") (part "ERJ-8ENF1200V"))
    )
    (comp (ref "R121")
      (value "120")
      (footprint "R1206")
      (description "RES 120 OHM 1/4W 1% 1206 SMD")
      (fields
        (field (name "MANUFACTURER") "Panasonic - ECG")
        (field (name "MANUFACTURER PART NUMBER") "ERJ-8ENF1200V")
      )
      (libsource (lib "eRCL") (part "ERJ-8ENF1200V"))
    )
    (comp (ref "R122")
      (value "120")
      (footprint "R1206")
      (description "RES 120 OHM 1/4W 1% 1206 SMD")
      (fields
        (field (name "MANUFACTURER") "Panasonic - ECG")
        (field (name "MANUFACTURER PART NUMBER") "ERJ-8ENF1200V")
      )
      (libsource (lib "eRCL") (part "ERJ-8ENF1200V"))
    )
    (comp (ref "R126")
      (value "5.1k")
      (footprint "R0805")
      (description "RES 5.10K OHM 1/8W 1% 0805 SMD")
      (fields
        (field (name "MANUFACTURER") "Panasonic - ECG")
        (field (name "MANUFACTURER PART NUMBER") "ERJ-6ENF5101V")
      )
      (libsource (lib "eRCL") (part "ERJ-6ENF5101V"))
    )
    (comp (ref "R127")
      (value "5.1k")
      (footprint "R0805")
      (description "RES 5.10K OHM 1/8W 1% 0805 SMD")
      (fields
        (field (name "MANUFACTURER") "Panasonic - ECG")
        (field (name "MANUFACTURER PART NUMBER") "ERJ-6ENF5101V")
      )
      (libsource (lib "eRCL") (part "ERJ-6ENF5101V"))
    )
    (comp (ref "R128")
      (value "5.1k")
      (footprint "R0805")
      (description "RES 5.10K OHM 1/8W 1% 0805 SMD")
      (fields
        (field (name "MANUFACTURER") "Panasonic - ECG")
        (field (name "MANUFACTURER PART NUMBER") "ERJ-6ENF5101V")
      )
      (libsource (lib "eRCL") (part "ERJ-6ENF5101V"))
    )
    (comp (ref "R132")
      (value "120")
      (footprint "R1206")
      (description "RES 120 OHM 1/4W 1% 1206 SMD")
      (fields
        (field (name "MANUFACTURER") "Panasonic - ECG")
        (field (name "MANUFACTURER PART NUMBER") "ERJ-8ENF1200V")
      )
      (libsource (lib "eRCL") (part "ERJ-8ENF1200V"))
    )
    (comp (ref "R133")
      (value "120")
      (footprint "R1206")
      (description "RES 120 OHM 1/4W 1% 1206 SMD")
      (fields
        (field (name "MANUFACTURER") "Panasonic - ECG")
        (field (name "MANUFACTURER PART NUMBER") "ERJ-8ENF1200V")
      )
      (libsource (lib "eRCL") (part "ERJ-8ENF1200V"))
    )
    (comp (ref "R134")
      (value "120")
      (footprint "R1206")
      (description "RES 120 OHM 1/4W 1% 1206 SMD")
      (fields
        (field (name "MANUFACTURER") "Panasonic - ECG")
        (field (name "MANUFACTURER PART NUMBER") "ERJ-8ENF1200V")
      )
      (libsource (lib "eRCL") (part "ERJ-8ENF1200V"))
    )
    (comp (ref "R138")
      (value "120")
      (footprint "R1206")
      (description "RES 120 OHM 1/4W 1% 1206 SMD")
      (fields
        (field (name "MANUFACTURER") "Panasonic - ECG")
        (field (name "MANUFACTURER PART NUMBER") "ERJ-8ENF1200V")
      )
      (libsource (lib "eRCL") (part "ERJ-8ENF1200V"))
    )
    (comp (ref "R139")
      (value "120")
      (footprint "R1206")
      (description "RES 120 OHM 1/4W 1% 1206 SMD")
      (fields
        (field (name "MANUFACTURER") "Panasonic - ECG")
        (field (name "MANUFACTURER PART NUMBER") "ERJ-8ENF1200V")
      )
      (libsource (lib "eRCL") (part "ERJ-8ENF1200V"))
    )
    (comp (ref "R140")
      (value "120")
      (footprint "R1206")
      (description "RES 120 OHM 1/4W 1% 1206 SMD")
      (fields
        (field (name "MANUFACTURER") "Panasonic - ECG")
        (field (name "MANUFACTURER PART NUMBER") "ERJ-8ENF1200V")
      )
      (libsource (lib "eRCL") (part "ERJ-8ENF1200V"))
    )
    (comp (ref "R144")
      (value "5.1k")
      (footprint "R0805")
      (description "RES 5.10K OHM 1/8W 1% 0805 SMD")
      (fields
        (field (name "MANUFACTURER") "Panasonic - ECG")
        (field (name "MANUFACTURER PART NUMBER") "ERJ-6ENF5101V")
      )
      (libsource (lib "eRCL") (part "ERJ-6ENF5101V"))
    )
    (comp (ref "R145")
      (value "5.1k")
      (footprint "R0805")
      (description "RES 5.10K OHM 1/8W 1% 0805 SMD")
      (fields
        (field (name "MANUFACTURER") "Panasonic - ECG")
        (field (name "MANUFACTURER PART NUMBER") "ERJ-6ENF5101V")
      )
      (libsource (lib "eRCL") (part "ERJ-6ENF5101V"))
    )
    (comp (ref "R146")
      (value "5.1k")
      (footprint "R0805")
      (description "RES 5.10K OHM 1/8W 1% 0805 SMD")
      (fields
        (field (name "MANUFACTURER") "Panasonic - ECG")
        (field (name "MANUFACTURER PART NUMBER") "ERJ-6ENF5101V")
      )
      (libsource (lib "eRCL") (part "ERJ-6ENF5101V"))
    )
    (comp (ref "R150")
      (value "120")
      (footprint "R1206")
      (description "RES 120 OHM 1/4W 1% 1206 SMD")
      (fields
        (field (name "MANUFACTURER") "Panasonic - ECG")
        (field (name "MANUFACTURER PART NUMBER") "ERJ-8ENF1200V")
      )
      (libsource (lib "eRCL") (part "ERJ-8ENF1200V"))
    )
    (comp (ref "R151")
      (value "120")
      (footprint "R1206")
      (description "RES 120 OHM 1/4W 1% 1206 SMD")
      (fields
        (field (name "MANUFACTURER") "Panasonic - ECG")
        (field (name "MANUFACTURER PART NUMBER") "ERJ-8ENF1200V")
      )
      (libsource (lib "eRCL") (part "ERJ-8ENF1200V"))
    )
    (comp (ref "R152")
      (value "120")
      (footprint "R1206")
      (description "RES 120 OHM 1/4W 1% 1206 SMD")
      (fields
        (field (name "MANUFACTURER") "Panasonic - ECG")
        (field (name "MANUFACTURER PART NUMBER") "ERJ-8ENF1200V")
      )
      (libsource (lib "eRCL") (part "ERJ-8ENF1200V"))
    )
    (comp (ref "R156")
      (value "120")
      (footprint "R1206")
      (description "RES 120 OHM 1/4W 1% 1206 SMD")
      (fields
        (field (name "MANUFACTURER") "Panasonic - ECG")
        (field (name "MANUFACTURER PART NUMBER") "ERJ-8ENF1200V")
      )
      (libsource (lib "eRCL") (part "ERJ-8ENF1200V"))
    )
    (comp (ref "R157")
      (value "120")
      (footprint "R1206")
      (description "RES 120 OHM 1/4W 1% 1206 SMD")
      (fields
        (field (name "MANUFACTURER") "Panasonic - ECG")
        (field (name "MANUFACTURER PART NUMBER") "ERJ-8ENF1200V")
      )
      (libsource (lib "eRCL") (part "ERJ-8ENF1200V"))
    )
    (comp (ref "R158")
      (value "120")
      (footprint "R1206")
      (description "RES 120 OHM 1/4W 1% 1206 SMD")
      (fields
        (field (name "MANUFACTURER") "Panasonic - ECG")
        (field (name "MANUFACTURER PART NUMBER") "ERJ-8ENF1200V")
      )
      (libsource (lib "eRCL") (part "ERJ-8ENF1200V"))
    )
    (comp (ref "R162")
      (value "5.1k")
      (footprint "R0805")
      (description "RES 5.10K OHM 1/8W 1% 0805 SMD")
      (fields
        (field (name "MANUFACTURER") "Panasonic - ECG")
        (field (name "MANUFACTURER PART NUMBER") "ERJ-6ENF5101V")
      )
      (libsource (lib "eRCL") (part "ERJ-6ENF5101V"))
    )
    (comp (ref "R163")
      (value "5.1k")
      (footprint "R0805")
      (description "RES 5.10K OHM 1/8W 1% 0805 SMD")
      (fields
        (field (name "MANUFACTURER") "Panasonic - ECG")
        (field (name "MANUFACTURER PART NUMBER") "ERJ-6ENF5101V")
      )
      (libsource (lib "eRCL") (part "ERJ-6ENF5101V"))
    )
    (comp (ref "R164")
      (value "5.1k")
      (footprint "R0805")
      (description "RES 5.10K OHM 1/8W 1% 0805 SMD")
      (fields
        (field (name "MANUFACTURER") "Panasonic - ECG")
        (field (name "MANUFACTURER PART NUMBER") "ERJ-6ENF5101V")
      )
      (libsource (lib "eRCL") (part "ERJ-6ENF5101V"))
    )
    (comp (ref "R168")
      (value "120")
      (footprint "R1206")
      (description "RES 120 OHM 1/4W 1% 1206 SMD")
      (fields
        (field (name "MANUFACTURER") "Panasonic - ECG")
        (field (name "MANUFACTURER PART NUMBER") "ERJ-8ENF1200V")
      )
      (libsource (lib "eRCL") (part "ERJ-8ENF1200V"))
    )
    (comp (ref "R169")
      (value "120")
      (footprint "R1206")
      (description "RES 120 OHM 1/4W 1% 1206 SMD")
      (fields
        (field (name "MANUFACTURER") "Panasonic - ECG")
        (field (name "MANUFACTURER PART NUMBER") "ERJ-8ENF1200V")
      )
      (libsource (lib "eRCL") (part "ERJ-8ENF1200V"))
    )
    (comp (ref "R170")
      (value "120")
      (footprint "R1206")
      (description "RES 120 OHM 1/4W 1% 1206 SMD")
      (fields
        (field (name "MANUFACTURER") "Panasonic - ECG")
        (field (name "MANUFACTURER PART NUMBER") "ERJ-8ENF1200V")
      )
      (libsource (lib "eRCL") (part "ERJ-8ENF1200V"))
    )
    (comp (ref "R174")
      (value "120")
      (footprint "R1206")
      (description "RES 120 OHM 1/4W 1% 1206 SMD")
      (fields
        (field (name "MANUFACTURER") "Panasonic - ECG")
        (field (name "MANUFACTURER PART NUMBER") "ERJ-8ENF1200V")
      )
      (libsource (lib "eRCL") (part "ERJ-8ENF1200V"))
    )
    (comp (ref "R175")
      (value "120")
      (footprint "R1206")
      (description "RES 120 OHM 1/4W 1% 1206 SMD")
      (fields
        (field (name "MANUFACTURER") "Panasonic - ECG")
        (field (name "MANUFACTURER PART NUMBER") "ERJ-8ENF1200V")
      )
      (libsource (lib "eRCL") (part "ERJ-8ENF1200V"))
    )
    (comp (ref "R176")
      (value "120")
      (footprint "R1206")
      (description "RES 120 OHM 1/4W 1% 1206 SMD")
      (fields
        (field (name "MANUFACTURER") "Panasonic - ECG")
        (field (name "MANUFACTURER PART NUMBER") "ERJ-8ENF1200V")
      )
      (libsource (lib "eRCL") (part "ERJ-8ENF1200V"))
    )
    (comp (ref "R180")
      (value "5.1k")
      (footprint "R0805")
      (description "RES 5.10K OHM 1/8W 1% 0805 SMD")
      (fields
        (field (name "MANUFACTURER") "Panasonic - ECG")
        (field (name "MANUFACTURER PART NUMBER") "ERJ-6ENF5101V")
      )
      (libsource (lib "eRCL") (part "ERJ-6ENF5101V"))
    )
    (comp (ref "R181")
      (value "5.1k")
      (footprint "R0805")
      (description "RES 5.10K OHM 1/8W 1% 0805 SMD")
      (fields
        (field (name "MANUFACTURER") "Panasonic - ECG")
        (field (name "MANUFACTURER PART NUMBER") "ERJ-6ENF5101V")
      )
      (libsource (lib "eRCL") (part "ERJ-6ENF5101V"))
    )
    (comp (ref "R182")
      (value "5.1k")
      (footprint "R0805")
      (description "RES 5.10K OHM 1/8W 1% 0805 SMD")
      (fields
        (field (name "MANUFACTURER") "Panasonic - ECG")
        (field (name "MANUFACTURER PART NUMBER") "ERJ-6ENF5101V")
      )
      (libsource (lib "eRCL") (part "ERJ-6ENF5101V"))
    )
    (comp (ref "R186")
      (value "120")
      (footprint "R1206")
      (description "RES 120 OHM 1/4W 1% 1206 SMD")
      (fields
        (field (name "MANUFACTURER") "Panasonic - ECG")
        (field (name "MANUFACTURER PART NUMBER") "ERJ-8ENF1200V")
      )
      (libsource (lib "eRCL") (part "ERJ-8ENF1200V"))
    )
    (comp (ref "R187")
      (value "120")
      (footprint "R1206")
      (description "RES 120 OHM 1/4W 1% 1206 SMD")
      (fields
        (field (name "MANUFACTURER") "Panasonic - ECG")
        (field (name "MANUFACTURER PART NUMBER") "ERJ-8ENF1200V")
      )
      (libsource (lib "eRCL") (part "ERJ-8ENF1200V"))
    )
    (comp (ref "R188")
      (value "120")
      (footprint "R1206")
      (description "RES 120 OHM 1/4W 1% 1206 SMD")
      (fields
        (field (name "MANUFACTURER") "Panasonic - ECG")
        (field (name "MANUFACTURER PART NUMBER") "ERJ-8ENF1200V")
      )
      (libsource (lib "eRCL") (part "ERJ-8ENF1200V"))
    )
    (comp (ref "R192")
      (value "120")
      (footprint "R1206")
      (description "RES 120 OHM 1/4W 1% 1206 SMD")
      (fields
        (field (name "MANUFACTURER") "Panasonic - ECG")
        (field (name "MANUFACTURER PART NUMBER") "ERJ-8ENF1200V")
      )
      (libsource (lib "eRCL") (part "ERJ-8ENF1200V"))
    )
    (comp (ref "R193")
      (value "120")
      (footprint "R1206")
      (description "RES 120 OHM 1/4W 1% 1206 SMD")
      (fields
        (field (name "MANUFACTURER") "Panasonic - ECG")
        (field (name "MANUFACTURER PART NUMBER") "ERJ-8ENF1200V")
      )
      (libsource (lib "eRCL") (part "ERJ-8ENF1200V"))
    )
    (comp (ref "R194")
      (value "120")
      (footprint "R1206")
      (description "RES 120 OHM 1/4W 1% 1206 SMD")
      (fields
        (field (name "MANUFACTURER") "Panasonic - ECG")
        (field (name "MANUFACTURER PART NUMBER") "ERJ-8ENF1200V")
      )
      (libsource (lib "eRCL") (part "ERJ-8ENF1200V"))
    )
    (comp (ref "R198")
      (value "5.1k")
      (footprint "R0805")
      (description "RES 5.10K OHM 1/8W 1% 0805 SMD")
      (fields
        (field (name "MANUFACTURER") "Panasonic - ECG")
        (field (name "MANUFACTURER PART NUMBER") "ERJ-6ENF5101V")
      )
      (libsource (lib "eRCL") (part "ERJ-6ENF5101V"))
    )
    (comp (ref "R199")
      (value "5.1k")
      (footprint "R0805")
      (description "RES 5.10K OHM 1/8W 1% 0805 SMD")
      (fields
        (field (name "MANUFACTURER") "Panasonic - ECG")
        (field (name "MANUFACTURER PART NUMBER") "ERJ-6ENF5101V")
      )
      (libsource (lib "eRCL") (part "ERJ-6ENF5101V"))
    )
    (comp (ref "R200")
      (value "5.1k")
      (footprint "R0805")
      (description "RES 5.10K OHM 1/8W 1% 0805 SMD")
      (fields
        (field (name "MANUFACTURER") "Panasonic - ECG")
        (field (name "MANUFACTURER PART NUMBER") "ERJ-6ENF5101V")
      )
      (libsource (lib "eRCL") (part "ERJ-6ENF5101V"))
    )
    (comp (ref "R204")
      (value "120")
      (footprint "R1206")
      (description "RES 120 OHM 1/4W 1% 1206 SMD")
      (fields
        (field (name "MANUFACTURER") "Panasonic - ECG")
        (field (name "MANUFACTURER PART NUMBER") "ERJ-8ENF1200V")
      )
      (libsource (lib "eRCL") (part "ERJ-8ENF1200V"))
    )
    (comp (ref "R205")
      (value "120")
      (footprint "R1206")
      (description "RES 120 OHM 1/4W 1% 1206 SMD")
      (fields
        (field (name "MANUFACTURER") "Panasonic - ECG")
        (field (name "MANUFACTURER PART NUMBER") "ERJ-8ENF1200V")
      )
      (libsource (lib "eRCL") (part "ERJ-8ENF1200V"))
    )
    (comp (ref "R206")
      (value "120")
      (footprint "R1206")
      (description "RES 120 OHM 1/4W 1% 1206 SMD")
      (fields
        (field (name "MANUFACTURER") "Panasonic - ECG")
        (field (name "MANUFACTURER PART NUMBER") "ERJ-8ENF1200V")
      )
      (libsource (lib "eRCL") (part "ERJ-8ENF1200V"))
    )
    (comp (ref "R210")
      (value "120")
      (footprint "R1206")
      (description "RES 120 OHM 1/4W 1% 1206 SMD")
      (fields
        (field (name "MANUFACTURER") "Panasonic - ECG")
        (field (name "MANUFACTURER PART NUMBER") "ERJ-8ENF1200V")
      )
      (libsource (lib "eRCL") (part "ERJ-8ENF1200V"))
    )
    (comp (ref "R211")
      (value "120")
      (footprint "R1206")
      (description "RES 120 OHM 1/4W 1% 1206 SMD")
      (fields
        (field (name "MANUFACTURER") "Panasonic - ECG")
        (field (name "MANUFACTURER PART NUMBER") "ERJ-8ENF1200V")
      )
      (libsource (lib "eRCL") (part "ERJ-8ENF1200V"))
    )
    (comp (ref "R212")
      (value "120")
      (footprint "R1206")
      (description "RES 120 OHM 1/4W 1% 1206 SMD")
      (fields
        (field (name "MANUFACTURER") "Panasonic - ECG")
        (field (name "MANUFACTURER PART NUMBER") "ERJ-8ENF1200V")
      )
      (libsource (lib "eRCL") (part "ERJ-8ENF1200V"))
    )
    (comp (ref "R216")
      (value "5.1k")
      (footprint "R0805")
      (description "RES 5.10K OHM 1/8W 1% 0805 SMD")
      (fields
        (field (name "MANUFACTURER") "Panasonic - ECG")
        (field (name "MANUFACTURER PART NUMBER") "ERJ-6ENF5101V")
      )
      (libsource (lib "eRCL") (part "ERJ-6ENF5101V"))
    )
    (comp (ref "R217")
      (value "5.1k")
      (footprint "R0805")
      (description "RES 5.10K OHM 1/8W 1% 0805 SMD")
      (fields
        (field (name "MANUFACTURER") "Panasonic - ECG")
        (field (name "MANUFACTURER PART NUMBER") "ERJ-6ENF5101V")
      )
      (libsource (lib "eRCL") (part "ERJ-6ENF5101V"))
    )
    (comp (ref "R218")
      (value "5.1k")
      (footprint "R0805")
      (description "RES 5.10K OHM 1/8W 1% 0805 SMD")
      (fields
        (field (name "MANUFACTURER") "Panasonic - ECG")
        (field (name "MANUFACTURER PART NUMBER") "ERJ-6ENF5101V")
      )
      (libsource (lib "eRCL") (part "ERJ-6ENF5101V"))
    )
    (comp (ref "R222")
      (value "120")
      (footprint "R1206")
      (description "RES 120 OHM 1/4W 1% 1206 SMD")
      (fields
        (field (name "MANUFACTURER") "Panasonic - ECG")
        (field (name "MANUFACTURER PART NUMBER") "ERJ-8ENF1200V")
      )
      (libsource (lib "eRCL") (part "ERJ-8ENF1200V"))
    )
    (comp (ref "R223")
      (value "120")
      (footprint "R1206")
      (description "RES 120 OHM 1/4W 1% 1206 SMD")
      (fields
        (field (name "MANUFACTURER") "Panasonic - ECG")
        (field (name "MANUFACTURER PART NUMBER") "ERJ-8ENF1200V")
      )
      (libsource (lib "eRCL") (part "ERJ-8ENF1200V"))
    )
    (comp (ref "R224")
      (value "120")
      (footprint "R1206")
      (description "RES 120 OHM 1/4W 1% 1206 SMD")
      (fields
        (field (name "MANUFACTURER") "Panasonic - ECG")
        (field (name "MANUFACTURER PART NUMBER") "ERJ-8ENF1200V")
      )
      (libsource (lib "eRCL") (part "ERJ-8ENF1200V"))
    )
    (comp (ref "R228")
      (value "120")
      (footprint "R1206")
      (description "RES 120 OHM 1/4W 1% 1206 SMD")
      (fields
        (field (name "MANUFACTURER") "Panasonic - ECG")
        (field (name "MANUFACTURER PART NUMBER") "ERJ-8ENF1200V")
      )
      (libsource (lib "eRCL") (part "ERJ-8ENF1200V"))
    )
    (comp (ref "R229")
      (value "120")
      (footprint "R1206")
      (description "RES 120 OHM 1/4W 1% 1206 SMD")
      (fields
        (field (name "MANUFACTURER") "Panasonic - ECG")
        (field (name "MANUFACTURER PART NUMBER") "ERJ-8ENF1200V")
      )
      (libsource (lib "eRCL") (part "ERJ-8ENF1200V"))
    )
    (comp (ref "R230")
      (value "120")
      (footprint "R1206")
      (description "RES 120 OHM 1/4W 1% 1206 SMD")
      (fields
        (field (name "MANUFACTURER") "Panasonic - ECG")
        (field (name "MANUFACTURER PART NUMBER") "ERJ-8ENF1200V")
      )
      (libsource (lib "eRCL") (part "ERJ-8ENF1200V"))
    )
    (comp (ref "U22")
      (value "IS/SN74HC573DWZ")
      (footprint "SOIC300-20")
      (description "Octal D-Type Transparent Latch with 3-State Outputs")
      (fields
        (field (name "MANUFACTURER") "NXP Semiconductors")
        (field (name "MANUFACTURER PART NUMBER") "74HC573D-T")
        (field (name "SOURCE") "Digikey")
      )
      (libsource (lib "ScoreBoard") (part "IS/SN74HC573DWZ"))
    )
    (comp (ref "U23")
      (value "IS/SN74HC573DWZ")
      (footprint "SOIC300-20")
      (description "Octal D-Type Transparent Latch with 3-State Outputs")
      (fields
        (field (name "MANUFACTURER") "NXP Semiconductors")
        (field (name "MANUFACTURER PART NUMBER") "74HC573D-T")
        (field (name "SOURCE") "Digikey")
      )
      (libsource (lib "ScoreBoard") (part "IS/SN74HC573DWZ"))
    )
    (comp (ref "U24")
      (value "IS/SN74HC573DWZ")
      (footprint "SOIC300-20")
      (description "Octal D-Type Transparent Latch with 3-State Outputs")
      (fields
        (field (name "MANUFACTURER") "NXP Semiconductors")
        (field (name "MANUFACTURER PART NUMBER") "74HC573D-T")
        (field (name "SOURCE") "Digikey")
      )
      (libsource (lib "ScoreBoard") (part "IS/SN74HC573DWZ"))
    )
  )
  (nets
    (net (code "1") (name "/8V") (class "Default")
      (node (ref "DS103") (pin "1") (pinfunction "A_1") (pintype "passive"))
      (node (ref "DS105") (pin "1") (pinfunction "A_1") (pintype "passive"))
      (node (ref "DS107") (pin "1") (pinfunction "A_1") (pintype "passive"))
      (node (ref "DS11") (pin "1") (pinfunction "A_1") (pintype "passive"))
      (node (ref "DS115") (pin "1") (pinfunction "A_1") (pintype "passive"))
      (node (ref "DS117") (pin "1") (pinfunction "A_1") (pintype "passive"))
      (node (ref "DS119") (pin "1") (pinfunction "A_1") (pintype "passive"))
      (node (ref "DS127") (pin "1") (pinfunction "A_1") (pintype "passive"))
      (node (ref "DS129") (pin "1") (pinfunction "A_1") (pintype "passive"))
      (node (ref "DS131") (pin "1") (pinfunction "A_1") (pintype "passive"))
      (node (ref "DS139") (pin "1") (pinfunction "A_1") (pintype "passive"))
      (node (ref "DS141") (pin "1") (pinfunction "A_1") (pintype "passive"))
      (node (ref "DS143") (pin "1") (pinfunction "A_1") (pintype "passive"))
      (node (ref "DS151") (pin "1") (pinfunction "A_1") (pintype "passive"))
      (node (ref "DS153") (pin "1") (pinfunction "A_1") (pintype "passive"))
      (node (ref "DS155") (pin "1") (pinfunction "A_1") (pintype "passive"))
      (node (ref "DS163") (pin "1") (pinfunction "A_1") (pintype "passive"))
      (node (ref "DS165") (pin "1") (pinfunction "A_1") (pintype "passive"))
      (node (ref "DS167") (pin "1") (pinfunction "A_1") (pintype "passive"))
      (node (ref "DS19") (pin "1") (pinfunction "A_1") (pintype "passive"))
      (node (ref "DS21") (pin "1") (pinfunction "A_1") (pintype "passive"))
      (node (ref "DS23") (pin "1") (pinfunction "A_1") (pintype "passive"))
      (node (ref "DS31") (pin "1") (pinfunction "A_1") (pintype "passive"))
      (node (ref "DS33") (pin "1") (pinfunction "A_1") (pintype "passive"))
      (node (ref "DS35") (pin "1") (pinfunction "A_1") (pintype "passive"))
      (node (ref "DS43") (pin "1") (pinfunction "A_1") (pintype "passive"))
      (node (ref "DS45") (pin "1") (pinfunction "A_1") (pintype "passive"))
      (node (ref "DS47") (pin "1") (pinfunction "A_1") (pintype "passive"))
      (node (ref "DS55") (pin "1") (pinfunction "A_1") (pintype "passive"))
      (node (ref "DS57") (pin "1") (pinfunction "A_1") (pintype "passive"))
      (node (ref "DS59") (pin "1") (pinfunction "A_1") (pintype "passive"))
      (node (ref "DS67") (pin "1") (pinfunction "A_1") (pintype "passive"))
      (node (ref "DS69") (pin "1") (pinfunction "A_1") (pintype "passive"))
      (node (ref "DS7") (pin "1") (pinfunction "A_1") (pintype "passive"))
      (node (ref "DS71") (pin "1") (pinfunction "A_1") (pintype "passive"))
      (node (ref "DS79") (pin "1") (pinfunction "A_1") (pintype "passive"))
      (node (ref "DS81") (pin "1") (pinfunction "A_1") (pintype "passive"))
      (node (ref "DS83") (pin "1") (pinfunction "A_1") (pintype "passive"))
      (node (ref "DS9") (pin "1") (pinfunction "A_1") (pintype "passive"))
      (node (ref "DS91") (pin "1") (pinfunction "A_1") (pintype "passive"))
      (node (ref "DS93") (pin "1") (pinfunction "A_1") (pintype "passive"))
      (node (ref "DS95") (pin "1") (pinfunction "A_1") (pintype "passive"))
    )
    (net (code "2") (name "/CLK3") (class "Default")
      (node (ref "U22") (pin "11") (pinfunction "LE_11") (pintype "input"))
    )
    (net (code "3") (name "/CLK4") (class "Default")
      (node (ref "U23") (pin "11") (pinfunction "LE_11") (pintype "input"))
    )
    (net (code "4") (name "/CLK5") (class "Default")
      (node (ref "U24") (pin "11") (pinfunction "LE_11") (pintype "input"))
    )
    (net (code "5") (name "/D0") (class "Default")
      (node (ref "U22") (pin "2") (pinfunction "D1_2") (pintype "input"))
      (node (ref "U23") (pin "2") (pinfunction "D1_2") (pintype "input"))
      (node (ref "U24") (pin "2") (pinfunction "D1_2") (pintype "input"))
    )
    (net (code "6") (name "/D1") (class "Default")
      (node (ref "U22") (pin "3") (pinfunction "D2_3") (pintype "input"))
      (node (ref "U23") (pin "3") (pinfunction "D2_3") (pintype "input"))
      (node (ref "U24") (pin "3") (pinfunction "D2_3") (pintype "input"))
    )
    (net (code "7") (name "/D2") (class "Default")
      (node (ref "U22") (pin "4") (pinfunction "D3_4") (pintype "input"))
      (node (ref "U23") (pin "4") (pinfunction "D3_4") (pintype "input"))
      (node (ref "U24") (pin "4") (pinfunction "D3_4") (pintype "input"))
    )
    (net (code "8") (name "/D3") (class "Default")
      (node (ref "U22") (pin "5") (pinfunction "D4_5") (pintype "input"))
      (node (ref "U23") (pin "5") (pinfunction "D4_5") (pintype "input"))
      (node (ref "U24") (pin "5") (pinfunction "D4_5") (pintype "input"))
    )
    (net (code "9") (name "/D4") (class "Default")
      (node (ref "U22") (pin "6") (pinfunction "D5_6") (pintype "input"))
      (node (ref "U23") (pin "6") (pinfunction "D5_6") (pintype "input"))
      (node (ref "U24") (pin "6") (pinfunction "D5_6") (pintype "input"))
    )
    (net (code "10") (name "/D5") (class "Default")
      (node (ref "U22") (pin "7") (pinfunction "D6_7") (pintype "input"))
      (node (ref "U23") (pin "7") (pinfunction "D6_7") (pintype "input"))
      (node (ref "U24") (pin "7") (pinfunction "D6_7") (pintype "input"))
    )
    (net (code "11") (name "/D6") (class "Default")
      (node (ref "U22") (pin "8") (pinfunction "D7_8") (pintype "input"))
      (node (ref "U23") (pin "8") (pinfunction "D7_8") (pintype "input"))
      (node (ref "U24") (pin "8") (pinfunction "D7_8") (pintype "input"))
    )
    (net (code "12") (name "/D7") (class "Default")
      (node (ref "U22") (pin "9") (pinfunction "D8_9") (pintype "input"))
      (node (ref "U23") (pin "9") (pinfunction "D8_9") (pintype "input"))
      (node (ref "U24") (pin "9") (pinfunction "D8_9") (pintype "input"))
    )
    (net (code "13") (name "/LAMP3") (class "Default")
      (node (ref "U22") (pin "12") (pinfunction "Q8_12") (pintype "tri_state"))
    )
    (net (code "14") (name "/LAMP4") (class "Default")
      (node (ref "U23") (pin "12") (pinfunction "Q8_12") (pintype "tri_state"))
    )
    (net (code "15") (name "/LAMP5") (class "Default")
      (node (ref "U24") (pin "12") (pinfunction "Q8_12") (pintype "tri_state"))
    )
    (net (code "16") (name "/~{LED_OE}") (class "Default")
      (node (ref "U22") (pin "1") (pinfunction "~{OE}_1") (pintype "input"))
      (node (ref "U23") (pin "1") (pinfunction "~{OE}_1") (pintype "input"))
      (node (ref "U24") (pin "1") (pinfunction "~{OE}_1") (pintype "input"))
    )
    (net (code "17") (name "GND") (class "Default")
      (node (ref "C50") (pin "2") (pinfunction "2_2") (pintype "passive"))
      (node (ref "C51") (pin "2") (pinfunction "2_2") (pintype "passive"))
      (node (ref "C52") (pin "2") (pinfunction "2_2") (pintype "passive"))
      (node (ref "Q25") (pin "2") (pinfunction "E_2") (pintype "passive"))
      (node (ref "Q26") (pin "2") (pinfunction "E_2") (pintype "passive"))
      (node (ref "Q27") (pin "2") (pinfunction "E_2") (pintype "passive"))
      (node (ref "Q31") (pin "2") (pinfunction "E_2") (pintype "passive"))
      (node (ref "Q32") (pin "2") (pinfunction "E_2") (pintype "passive"))
      (node (ref "Q33") (pin "2") (pinfunction "E_2") (pintype "passive"))
      (node (ref "Q37") (pin "2") (pinfunction "E_2") (pintype "passive"))
      (node (ref "Q38") (pin "2") (pinfunction "E_2") (pintype "passive"))
      (node (ref "Q39") (pin "2") (pinfunction "E_2") (pintype "passive"))
      (node (ref "Q43") (pin "2") (pinfunction "E_2") (pintype "passive"))
      (node (ref "Q44") (pin "2") (pinfunction "E_2") (pintype "passive"))
      (node (ref "Q45") (pin "2") (pinfunction "E_2") (pintype "passive"))
      (node (ref "Q49") (pin "2") (pinfunction "E_2") (pintype "passive"))
      (node (ref "Q50") (pin "2") (pinfunction "E_2") (pintype "passive"))
      (node (ref "Q51") (pin "2") (pinfunction "E_2") (pintype "passive"))
      (node (ref "Q55") (pin "2") (pinfunction "E_2") (pintype "passive"))
      (node (ref "Q56") (pin "2") (pinfunction "E_2") (pintype "passive"))
      (node (ref "Q57") (pin "2") (pinfunction "E_2") (pintype "passive"))
      (node (ref "Q61") (pin "2") (pinfunction "E_2") (pintype "passive"))
      (node (ref "Q62") (pin "2") (pinfunction "E_2") (pintype "passive"))
      (node (ref "Q63") (pin "2") (pinfunction "E_2") (pintype "passive"))
      (node (ref "U22") (pin "10") (pinfunction "GND_10") (pintype "power_in"))
      (node (ref "U23") (pin "10") (pinfunction "GND_10") (pintype "power_in"))
      (node (ref "U24") (pin "10") (pinfunction "GND_10") (pintype "power_in"))
    )
    (net (code "18") (name "Net-(DS7-K)") (class "Default")
      (node (ref "DS7") (pin "2") (pinfunction "K_2") (pintype "passive"))
      (node (ref "DS8") (pin "1") (pinfunction "A_1") (pintype "passive"))
    )
    (net (code "19") (name "Net-(DS8-K)") (class "Default")
      (node (ref "DS8") (pin "2") (pinfunction "K_2") (pintype "passive"))
      (node (ref "R114") (pin "2") (pinfunction "2_2") (pintype "passive"))
    )
    (net (code "20") (name "Net-(DS10-A)") (class "Default")
      (node (ref "DS10") (pin "1") (pinfunction "A_1") (pintype "passive"))
      (node (ref "DS9") (pin "2") (pinfunction "K_2") (pintype "passive"))
    )
    (net (code "21") (name "Net-(DS10-K)") (class "Default")
      (node (ref "DS10") (pin "2") (pinfunction "K_2") (pintype "passive"))
      (node (ref "R115") (pin "2") (pinfunction "2_2") (pintype "passive"))
    )
    (net (code "22") (name "Net-(DS11-K)") (class "Default")
      (node (ref "DS11") (pin "2") (pinfunction "K_2") (pintype "passive"))
      (node (ref "DS12") (pin "1") (pinfunction "A_1") (pintype "passive"))
    )
    (net (code "23") (name "Net-(DS12-K)") (class "Default")
      (node (ref "DS12") (pin "2") (pinfunction "K_2") (pintype "passive"))
      (node (ref "R116") (pin "2") (pinfunction "2_2") (pintype "passive"))
    )
    (net (code "24") (name "Net-(DS19-K)") (class "Default")
      (node (ref "DS19") (pin "2") (pinfunction "K_2") (pintype "passive"))
      (node (ref "DS20") (pin "1") (pinfunction "A_1") (pintype "passive"))
    )
    (net (code "25") (name "Net-(DS20-K)") (class "Default")
      (node (ref "DS20") (pin "2") (pinfunction "K_2") (pintype "passive"))
      (node (ref "R120") (pin "2") (pinfunction "2_2") (pintype "passive"))
    )
    (net (code "26") (name "Net-(DS21-K)") (class "Default")
      (node (ref "DS21") (pin "2") (pinfunction "K_2") (pintype "passive"))
      (node (ref "DS22") (pin "1") (pinfunction "A_1") (pintype "passive"))
    )
    (net (code "27") (name "Net-(DS22-K)") (class "Default")
      (node (ref "DS22") (pin "2") (pinfunction "K_2") (pintype "passive"))
      (node (ref "R121") (pin "2") (pinfunction "2_2") (pintype "passive"))
    )
    (net (code "28") (name "Net-(DS23-K)") (class "Default")
      (node (ref "DS23") (pin "2") (pinfunction "K_2") (pintype "passive"))
      (node (ref "DS24") (pin "1") (pinfunction "A_1") (pintype "passive"))
    )
    (net (code "29") (name "Net-(DS24-K)") (class "Default")
      (node (ref "DS24") (pin "2") (pinfunction "K_2") (pintype "passive"))
      (node (ref "R122") (pin "2") (pinfunction "2_2") (pintype "passive"))
    )
    (net (code "30") (name "Net-(DS31-K)") (class "Default")
      (node (ref "DS31") (pin "2") (pinfunction "K_2") (pintype "passive"))
      (node (ref "DS32") (pin "1") (pinfunction "A_1") (pintype "passive"))
    )
    (net (code "31") (name "Net-(DS32-K)") (class "Default")
      (node (ref "DS32") (pin "2") (pinfunction "K_2") (pintype "passive"))
      (node (ref "R132") (pin "2") (pinfunction "2_2") (pintype "passive"))
    )
    (net (code "32") (name "Net-(DS33-K)") (class "Default")
      (node (ref "DS33") (pin "2") (pinfunction "K_2") (pintype "passive"))
      (node (ref "DS34") (pin "1") (pinfunction "A_1") (pintype "passive"))
    )
    (net (code "33") (name "Net-(DS34-K)") (class "Default")
      (node (ref "DS34") (pin "2") (pinfunction "K_2") (pintype "passive"))
      (node (ref "R133") (pin "2") (pinfunction "2_2") (pintype "passive"))
    )
    (net (code "34") (name "Net-(DS35-K)") (class "Default")
      (node (ref "DS35") (pin "2") (pinfunction "K_2") (pintype "passive"))
      (node (ref "DS36") (pin "1") (pinfunction "A_1") (pintype "passive"))
    )
    (net (code "35") (name "Net-(DS36-K)") (class "Default")
      (node (ref "DS36") (pin "2") (pinfunction "K_2") (pintype "passive"))
      (node (ref "R134") (pin "2") (pinfunction "2_2") (pintype "passive"))
    )
    (net (code "36") (name "Net-(DS43-K)") (class "Default")
      (node (ref "DS43") (pin "2") (pinfunction "K_2") (pintype "passive"))
      (node (ref "DS44") (pin "1") (pinfunction "A_1") (pintype "passive"))
    )
    (net (code "37") (name "Net-(DS44-K)") (class "Default")
      (node (ref "DS44") (pin "2") (pinfunction "K_2") (pintype "passive"))
      (node (ref "R138") (pin "2") (pinfunction "2_2") (pintype "passive"))
    )
    (net (code "38") (name "Net-(DS45-K)") (class "Default")
      (node (ref "DS45") (pin "2") (pinfunction "K_2") (pintype "passive"))
      (node (ref "DS46") (pin "1") (pinfunction "A_1") (pintype "passive"))
    )
    (net (code "39") (name "Net-(DS46-K)") (class "Default")
      (node (ref "DS46") (pin "2") (pinfunction "K_2") (pintype "passive"))
      (node (ref "R139") (pin "2") (pinfunction "2_2") (pintype "passive"))
    )
    (net (code "40") (name "Net-(DS47-K)") (class "Default")
      (node (ref "DS47") (pin "2") (pinfunction "K_2") (pintype "passive"))
      (node (ref "DS48") (pin "1") (pinfunction "A_1") (pintype "passive"))
    )
    (net (code "41") (name "Net-(DS48-K)") (class "Default")
      (node (ref "DS48") (pin "2") (pinfunction "K_2") (pintype "passive"))
      (node (ref "R140") (pin "2") (pinfunction "2_2") (pintype "passive"))
    )
    (net (code "42") (name "Net-(DS55-K)") (class "Default")
      (node (ref "DS55") (pin "2") (pinfunction "K_2") (pintype "passive"))
      (node (ref "DS56") (pin "1") (pinfunction "A_1") (pintype "passive"))
    )
    (net (code "43") (name "Net-(DS56-K)") (class "Default")
      (node (ref "DS56") (pin "2") (pinfunction "K_2") (pintype "passive"))
      (node (ref "R150") (pin "2") (pinfunction "2_2") (pintype "passive"))
    )
    (net (code "44") (name "Net-(DS57-K)") (class "Default")
      (node (ref "DS57") (pin "2") (pinfunction "K_2") (pintype "passive"))
      (node (ref "DS58") (pin "1") (pinfunction "A_1") (pintype "passive"))
    )
    (net (code "45") (name "Net-(DS58-K)") (class "Default")
      (node (ref "DS58") (pin "2") (pinfunction "K_2") (pintype "passive"))
      (node (ref "R151") (pin "2") (pinfunction "2_2") (pintype "passive"))
    )
    (net (code "46") (name "Net-(DS59-K)") (class "Default")
      (node (ref "DS59") (pin "2") (pinfunction "K_2") (pintype "passive"))
      (node (ref "DS60") (pin "1") (pinfunction "A_1") (pintype "passive"))
    )
    (net (code "47") (name "Net-(DS60-K)") (class "Default")
      (node (ref "DS60") (pin "2") (pinfunction "K_2") (pintype "passive"))
      (node (ref "R152") (pin "2") (pinfunction "2_2") (pintype "passive"))
    )
    (net (code "48") (name "Net-(DS67-K)") (class "Default")
      (node (ref "DS67") (pin "2") (pinfunction "K_2") (pintype "passive"))
      (node (ref "DS68") (pin "1") (pinfunction "A_1") (pintype "passive"))
    )
    (net (code "49") (name "Net-(DS68-K)") (class "Default")
      (node (ref "DS68") (pin "2") (pinfunction "K_2") (pintype "passive"))
      (node (ref "R156") (pin "2") (pinfunction "2_2") (pintype "passive"))
    )
    (net (code "50") (name "Net-(DS69-K)") (class "Default")
      (node (ref "DS69") (pin "2") (pinfunction "K_2") (pintype "passive"))
      (node (ref "DS70") (pin "1") (pinfunction "A_1") (pintype "passive"))
    )
    (net (code "51") (name "Net-(DS70-K)") (class "Default")
      (node (ref "DS70") (pin "2") (pinfunction "K_2") (pintype "passive"))
      (node (ref "R157") (pin "2") (pinfunction "2_2") (pintype "passive"))
    )
    (net (code "52") (name "Net-(DS71-K)") (class "Default")
      (node (ref "DS71") (pin "2") (pinfunction "K_2") (pintype "passive"))
      (node (ref "DS72") (pin "1") (pinfunction "A_1") (pintype "passive"))
    )
    (net (code "53") (name "Net-(DS72-K)") (class "Default")
      (node (ref "DS72") (pin "2") (pinfunction "K_2") (pintype "passive"))
      (node (ref "R158") (pin "2") (pinfunction "2_2") (pintype "passive"))
    )
    (net (code "54") (name "Net-(DS79-K)") (class "Default")
      (node (ref "DS79") (pin "2") (pinfunction "K_2") (pintype "passive"))
      (node (ref "DS80") (pin "1") (pinfunction "A_1") (pintype "passive"))
    )
    (net (code "55") (name "Net-(DS80-K)") (class "Default")
      (node (ref "DS80") (pin "2") (pinfunction "K_2") (pintype "passive"))
      (node (ref "R168") (pin "2") (pinfunction "2_2") (pintype "passive"))
    )
    (net (code "56") (name "Net-(DS81-K)") (class "Default")
      (node (ref "DS81") (pin "2") (pinfunction "K_2") (pintype "passive"))
      (node (ref "DS82") (pin "1") (pinfunction "A_1") (pintype "passive"))
    )
    (net (code "57") (name "Net-(DS82-K)") (class "Default")
      (node (ref "DS82") (pin "2") (pinfunction "K_2") (pintype "passive"))
      (node (ref "R169") (pin "2") (pinfunction "2_2") (pintype "passive"))
    )
    (net (code "58") (name "Net-(DS83-K)") (class "Default")
      (node (ref "DS83") (pin "2") (pinfunction "K_2") (pintype "passive"))
      (node (ref "DS84") (pin "1") (pinfunction "A_1") (pintype "passive"))
    )
    (net (code "59") (name "Net-(DS84-K)") (class "Default")
      (node (ref "DS84") (pin "2") (pinfunction "K_2") (pintype "passive"))
      (node (ref "R170") (pin "2") (pinfunction "2_2") (pintype "passive"))
    )
    (net (code "60") (name "Net-(DS91-K)") (class "Default")
      (node (ref "DS91") (pin "2") (pinfunction "K_2") (pintype "passive"))
      (node (ref "DS92") (pin "1") (pinfunction "A_1") (pintype "passive"))
    )
    (net (code "61") (name "Net-(DS92-K)") (class "Default")
      (node (ref "DS92") (pin "2") (pinfunction "K_2") (pintype "passive"))
      (node (ref "R174") (pin "2") (pinfunction "2_2") (pintype "passive"))
    )
    (net (code "62") (name "Net-(DS93-K)") (class "Default")
      (node (ref "DS93") (pin "2") (pinfunction "K_2") (pintype "passive"))
      (node (ref "DS94") (pin "1") (pinfunction "A_1") (pintype "passive"))
    )
    (net (code "63") (name "Net-(DS94-K)") (class "Default")
      (node (ref "DS94") (pin "2") (pinfunction "K_2") (pintype "passive"))
      (node (ref "R175") (pin "2") (pinfunction "2_2") (pintype "passive"))
    )
    (net (code "64") (name "Net-(DS95-K)") (class "Default")
      (node (ref "DS95") (pin "2") (pinfunction "K_2") (pintype "passive"))
      (node (ref "DS96") (pin "1") (pinfunction "A_1") (pintype "passive"))
    )
    (net (code "65") (name "Net-(DS96-K)") (class "Default")
      (node (ref "DS96") (pin "2") (pinfunction "K_2") (pintype "passive"))
      (node (ref "R176") (pin "2") (pinfunction "2_2") (pintype "passive"))
    )
    (net (code "66") (name "Net-(DS103-K)") (class "Default")
      (node (ref "DS103") (pin "2") (pinfunction "K_2") (pintype "passive"))
      (node (ref "DS104") (pin "1") (pinfunction "A_1") (pintype "passive"))
    )
    (net (code "67") (name "Net-(DS104-K)") (class "Default")
      (node (ref "DS104") (pin "2") (pinfunction "K_2") (pintype "passive"))
      (node (ref "R186") (pin "2") (pinfunction "2_2") (pintype "passive"))
    )
    (net (code "68") (name "Net-(DS105-K)") (class "Default")
      (node (ref "DS105") (pin "2") (pinfunction "K_2") (pintype "passive"))
      (node (ref "DS106") (pin "1") (pinfunction "A_1") (pintype "passive"))
    )
    (net (code "69") (name "Net-(DS106-K)") (class "Default")
      (node (ref "DS106") (pin "2") (pinfunction "K_2") (pintype "passive"))
      (node (ref "R187") (pin "2") (pinfunction "2_2") (pintype "passive"))
    )
    (net (code "70") (name "Net-(DS107-K)") (class "Default")
      (node (ref "DS107") (pin "2") (pinfunction "K_2") (pintype "passive"))
      (node (ref "DS108") (pin "1") (pinfunction "A_1") (pintype "passive"))
    )
    (net (code "71") (name "Net-(DS108-K)") (class "Default")
      (node (ref "DS108") (pin "2") (pinfunction "K_2") (pintype "passive"))
      (node (ref "R188") (pin "2") (pinfunction "2_2") (pintype "passive"))
    )
    (net (code "72") (name "Net-(DS115-K)") (class "Default")
      (node (ref "DS115") (pin "2") (pinfunction "K_2") (pintype "passive"))
      (node (ref "DS116") (pin "1") (pinfunction "A_1") (pintype "passive"))
    )
    (net (code "73") (name "Net-(DS116-K)") (class "Default")
      (node (ref "DS116") (pin "2") (pinfunction "K_2") (pintype "passive"))
      (node (ref "R192") (pin "2") (pinfunction "2_2") (pintype "passive"))
    )
    (net (code "74") (name "Net-(DS117-K)") (class "Default")
      (node (ref "DS117") (pin "2") (pinfunction "K_2") (pintype "passive"))
      (node (ref "DS118") (pin "1") (pinfunction "A_1") (pintype "passive"))
    )
    (net (code "75") (name "Net-(DS118-K)") (class "Default")
      (node (ref "DS118") (pin "2") (pinfunction "K_2") (pintype "passive"))
      (node (ref "R193") (pin "2") (pinfunction "2_2") (pintype "passive"))
    )
    (net (code "76") (name "Net-(DS119-K)") (class "Default")
      (node (ref "DS119") (pin "2") (pinfunction "K_2") (pintype "passive"))
      (node (ref "DS120") (pin "1") (pinfunction "A_1") (pintype "passive"))
    )
    (net (code "77") (name "Net-(DS120-K)") (class "Default")
      (node (ref "DS120") (pin "2") (pinfunction "K_2") (pintype "passive"))
      (node (ref "R194") (pin "2") (pinfunction "2_2") (pintype "passive"))
    )
    (net (code "78") (name "Net-(DS127-K)") (class "Default")
      (node (ref "DS127") (pin "2") (pinfunction "K_2") (pintype "passive"))
      (node (ref "DS128") (pin "1") (pinfunction "A_1") (pintype "passive"))
    )
    (net (code "79") (name "Net-(DS128-K)") (class "Default")
      (node (ref "DS128") (pin "2") (pinfunction "K_2") (pintype "passive"))
      (node (ref "R204") (pin "2") (pinfunction "2_2") (pintype "passive"))
    )
    (net (code "80") (name "Net-(DS129-K)") (class "Default")
      (node (ref "DS129") (pin "2") (pinfunction "K_2") (pintype "passive"))
      (node (ref "DS130") (pin "1") (pinfunction "A_1") (pintype "passive"))
    )
    (net (code "81") (name "Net-(DS130-K)") (class "Default")
      (node (ref "DS130") (pin "2") (pinfunction "K_2") (pintype "passive"))
      (node (ref "R205") (pin "2") (pinfunction "2_2") (pintype "passive"))
    )
    (net (code "82") (name "Net-(DS131-K)") (class "Default")
      (node (ref "DS131") (pin "2") (pinfunction "K_2") (pintype "passive"))
      (node (ref "DS132") (pin "1") (pinfunction "A_1") (pintype "passive"))
    )
    (net (code "83") (name "Net-(DS132-K)") (class "Default")
      (node (ref "DS132") (pin "2") (pinfunction "K_2") (pintype "passive"))
      (node (ref "R206") (pin "2") (pinfunction "2_2") (pintype "passive"))
    )
    (net (code "84") (name "Net-(DS139-K)") (class "Default")
      (node (ref "DS139") (pin "2") (pinfunction "K_2") (pintype "passive"))
      (node (ref "DS140") (pin "1") (pinfunction "A_1") (pintype "passive"))
    )
    (net (code "85") (name "Net-(DS140-K)") (class "Default")
      (node (ref "DS140") (pin "2") (pinfunction "K_2") (pintype "passive"))
      (node (ref "R210") (pin "2") (pinfunction "2_2") (pintype "passive"))
    )
    (net (code "86") (name "Net-(DS141-K)") (class "Default")
      (node (ref "DS141") (pin "2") (pinfunction "K_2") (pintype "passive"))
      (node (ref "DS142") (pin "1") (pinfunction "A_1") (pintype "passive"))
    )
    (net (code "87") (name "Net-(DS142-K)") (class "Default")
      (node (ref "DS142") (pin "2") (pinfunction "K_2") (pintype "passive"))
      (node (ref "R211") (pin "2") (pinfunction "2_2") (pintype "passive"))
    )
    (net (code "88") (name "Net-(DS143-K)") (class "Default")
      (node (ref "DS143") (pin "2") (pinfunction "K_2") (pintype "passive"))
      (node (ref "DS144") (pin "1") (pinfunction "A_1") (pintype "passive"))
    )
    (net (code "89") (name "Net-(DS144-K)") (class "Default")
      (node (ref "DS144") (pin "2") (pinfunction "K_2") (pintype "passive"))
      (node (ref "R212") (pin "2") (pinfunction "2_2") (pintype "passive"))
    )
    (net (code "90") (name "Net-(DS151-K)") (class "Default")
      (node (ref "DS151") (pin "2") (pinfunction "K_2") (pintype "passive"))
      (node (ref "DS152") (pin "1") (pinfunction "A_1") (pintype "passive"))
    )
    (net (code "91") (name "Net-(DS152-K)") (class "Default")
      (node (ref "DS152") (pin "2") (pinfunction "K_2") (pintype "passive"))
      (node (ref "R222") (pin "2") (pinfunction "2_2") (pintype "passive"))
    )
    (net (code "92") (name "Net-(DS153-K)") (class "Default")
      (node (ref "DS153") (pin "2") (pinfunction "K_2") (pintype "passive"))
      (node (ref "DS154") (pin "1") (pinfunction "A_1") (pintype "passive"))
    )
    (net (code "93") (name "Net-(DS154-K)") (class "Default")
      (node (ref "DS154") (pin "2") (pinfunction "K_2") (pintype "passive"))
      (node (ref "R223") (pin "2") (pinfunction "2_2") (pintype "passive"))
    )
    (net (code "94") (name "Net-(DS155-K)") (class "Default")
      (node (ref "DS155") (pin "2") (pinfunction "K_2") (pintype "passive"))
      (node (ref "DS156") (pin "1") (pinfunction "A_1") (pintype "passive"))
    )
    (net (code "95") (name "Net-(DS156-K)") (class "Default")
      (node (ref "DS156") (pin "2") (pinfunction "K_2") (pintype "passive"))
      (node (ref "R224") (pin "2") (pinfunction "2_2") (pintype "passive"))
    )
    (net (code "96") (name "Net-(DS163-K)") (class "Default")
      (node (ref "DS163") (pin "2") (pinfunction "K_2") (pintype "passive"))
      (node (ref "DS164") (pin "1") (pinfunction "A_1") (pintype "passive"))
    )
    (net (code "97") (name "Net-(DS164-K)") (class "Default")
      (node (ref "DS164") (pin "2") (pinfunction "K_2") (pintype "passive"))
      (node (ref "R228") (pin "2") (pinfunction "2_2") (pintype "passive"))
    )
    (net (code "98") (name "Net-(DS165-K)") (class "Default")
      (node (ref "DS165") (pin "2") (pinfunction "K_2") (pintype "passive"))
      (node (ref "DS166") (pin "1") (pinfunction "A_1") (pintype "passive"))
    )
    (net (code "99") (name "Net-(DS166-K)") (class "Default")
      (node (ref "DS166") (pin "2") (pinfunction "K_2") (pintype "passive"))
      (node (ref "R229") (pin "2") (pinfunction "2_2") (pintype "passive"))
    )
    (net (code "100") (name "Net-(DS167-K)") (class "Default")
      (node (ref "DS167") (pin "2") (pinfunction "K_2") (pintype "passive"))
      (node (ref "DS168") (pin "1") (pinfunction "A_1") (pintype "passive"))
    )
    (net (code "101") (name "Net-(DS168-K)") (class "Default")
      (node (ref "DS168") (pin "2") (pinfunction "K_2") (pintype "passive"))
      (node (ref "R230") (pin "2") (pinfunction "2_2") (pintype "passive"))
    )
    (net (code "102") (name "Net-(Q25-B)") (class "Default")
      (node (ref "Q25") (pin "1") (pinfunction "B_1") (pintype "passive"))
      (node (ref "R108") (pin "2") (pinfunction "2_2") (pintype "passive"))
    )
    (net (code "103") (name "Net-(Q25-C)") (class "Default")
      (node (ref "Q25") (pin "3") (pinfunction "C_3") (pintype "passive"))
      (node (ref "R114") (pin "1") (pinfunction "1_1") (pintype "passive"))
      (node (ref "R120") (pin "1") (pinfunction "1_1") (pintype "passive"))
    )
    (net (code "104") (name "Net-(Q26-B)") (class "Default")
      (node (ref "Q26") (pin "1") (pinfunction "B_1") (pintype "passive"))
      (node (ref "R109") (pin "2") (pinfunction "2_2") (pintype "passive"))
    )
    (net (code "105") (name "Net-(Q26-C)") (class "Default")
      (node (ref "Q26") (pin "3") (pinfunction "C_3") (pintype "passive"))
      (node (ref "R115") (pin "1") (pinfunction "1_1") (pintype "passive"))
      (node (ref "R121") (pin "1") (pinfunction "1_1") (pintype "passive"))
    )
    (net (code "106") (name "Net-(Q27-B)") (class "Default")
      (node (ref "Q27") (pin "1") (pinfunction "B_1") (pintype "passive"))
      (node (ref "R110") (pin "2") (pinfunction "2_2") (pintype "passive"))
    )
    (net (code "107") (name "Net-(Q27-C)") (class "Default")
      (node (ref "Q27") (pin "3") (pinfunction "C_3") (pintype "passive"))
      (node (ref "R116") (pin "1") (pinfunction "1_1") (pintype "passive"))
      (node (ref "R122") (pin "1") (pinfunction "1_1") (pintype "passive"))
    )
    (net (code "108") (name "Net-(Q31-B)") (class "Default")
      (node (ref "Q31") (pin "1") (pinfunction "B_1") (pintype "passive"))
      (node (ref "R126") (pin "2") (pinfunction "2_2") (pintype "passive"))
    )
    (net (code "109") (name "Net-(Q31-C)") (class "Default")
      (node (ref "Q31") (pin "3") (pinfunction "C_3") (pintype "passive"))
      (node (ref "R132") (pin "1") (pinfunction "1_1") (pintype "passive"))
      (node (ref "R138") (pin "1") (pinfunction "1_1") (pintype "passive"))
    )
    (net (code "110") (name "Net-(Q32-B)") (class "Default")
      (node (ref "Q32") (pin "1") (pinfunction "B_1") (pintype "passive"))
      (node (ref "R127") (pin "2") (pinfunction "2_2") (pintype "passive"))
    )
    (net (code "111") (name "Net-(Q32-C)") (class "Default")
      (node (ref "Q32") (pin "3") (pinfunction "C_3") (pintype "passive"))
      (node (ref "R133") (pin "1") (pinfunction "1_1") (pintype "passive"))
      (node (ref "R139") (pin "1") (pinfunction "1_1") (pintype "passive"))
    )
    (net (code "112") (name "Net-(Q33-B)") (class "Default")
      (node (ref "Q33") (pin "1") (pinfunction "B_1") (pintype "passive"))
      (node (ref "R128") (pin "2") (pinfunction "2_2") (pintype "passive"))
    )
    (net (code "113") (name "Net-(Q33-C)") (class "Default")
      (node (ref "Q33") (pin "3") (pinfunction "C_3") (pintype "passive"))
      (node (ref "R134") (pin "1") (pinfunction "1_1") (pintype "passive"))
      (node (ref "R140") (pin "1") (pinfunction "1_1") (pintype "passive"))
    )
    (net (code "114") (name "Net-(Q37-B)") (class "Default")
      (node (ref "Q37") (pin "1") (pinfunction "B_1") (pintype "passive"))
      (node (ref "R144") (pin "2") (pinfunction "2_2") (pintype "passive"))
    )
    (net (code "115") (name "Net-(Q37-C)") (class "Default")
      (node (ref "Q37") (pin "3") (pinfunction "C_3") (pintype "passive"))
      (node (ref "R150") (pin "1") (pinfunction "1_1") (pintype "passive"))
      (node (ref "R156") (pin "1") (pinfunction "1_1") (pintype "passive"))
    )
    (net (code "116") (name "Net-(Q38-B)") (class "Default")
      (node (ref "Q38") (pin "1") (pinfunction "B_1") (pintype "passive"))
      (node (ref "R145") (pin "2") (pinfunction "2_2") (pintype "passive"))
    )
    (net (code "117") (name "Net-(Q38-C)") (class "Default")
      (node (ref "Q38") (pin "3") (pinfunction "C_3") (pintype "passive"))
      (node (ref "R151") (pin "1") (pinfunction "1_1") (pintype "passive"))
      (node (ref "R157") (pin "1") (pinfunction "1_1") (pintype "passive"))
    )
    (net (code "118") (name "Net-(Q39-B)") (class "Default")
      (node (ref "Q39") (pin "1") (pinfunction "B_1") (pintype "passive"))
      (node (ref "R146") (pin "2") (pinfunction "2_2") (pintype "passive"))
    )
    (net (code "119") (name "Net-(Q39-C)") (class "Default")
      (node (ref "Q39") (pin "3") (pinfunction "C_3") (pintype "passive"))
      (node (ref "R152") (pin "1") (pinfunction "1_1") (pintype "passive"))
      (node (ref "R158") (pin "1") (pinfunction "1_1") (pintype "passive"))
    )
    (net (code "120") (name "Net-(Q43-B)") (class "Default")
      (node (ref "Q43") (pin "1") (pinfunction "B_1") (pintype "passive"))
      (node (ref "R162") (pin "2") (pinfunction "2_2") (pintype "passive"))
    )
    (net (code "121") (name "Net-(Q43-C)") (class "Default")
      (node (ref "Q43") (pin "3") (pinfunction "C_3") (pintype "passive"))
      (node (ref "R168") (pin "1") (pinfunction "1_1") (pintype "passive"))
      (node (ref "R174") (pin "1") (pinfunction "1_1") (pintype "passive"))
    )
    (net (code "122") (name "Net-(Q44-B)") (class "Default")
      (node (ref "Q44") (pin "1") (pinfunction "B_1") (pintype "passive"))
      (node (ref "R163") (pin "2") (pinfunction "2_2") (pintype "passive"))
    )
    (net (code "123") (name "Net-(Q44-C)") (class "Default")
      (node (ref "Q44") (pin "3") (pinfunction "C_3") (pintype "passive"))
      (node (ref "R169") (pin "1") (pinfunction "1_1") (pintype "passive"))
      (node (ref "R175") (pin "1") (pinfunction "1_1") (pintype "passive"))
    )
    (net (code "124") (name "Net-(Q45-B)") (class "Default")
      (node (ref "Q45") (pin "1") (pinfunction "B_1") (pintype "passive"))
      (node (ref "R164") (pin "2") (pinfunction "2_2") (pintype "passive"))
    )
    (net (code "125") (name "Net-(Q45-C)") (class "Default")
      (node (ref "Q45") (pin "3") (pinfunction "C_3") (pintype "passive"))
      (node (ref "R170") (pin "1") (pinfunction "1_1") (pintype "passive"))
      (node (ref "R176") (pin "1") (pinfunction "1_1") (pintype "passive"))
    )
    (net (code "126") (name "Net-(Q49-B)") (class "Default")
      (node (ref "Q49") (pin "1") (pinfunction "B_1") (pintype "passive"))
      (node (ref "R180") (pin "2") (pinfunction "2_2") (pintype "passive"))
    )
    (net (code "127") (name "Net-(Q49-C)") (class "Default")
      (node (ref "Q49") (pin "3") (pinfunction "C_3") (pintype "passive"))
      (node (ref "R186") (pin "1") (pinfunction "1_1") (pintype "passive"))
      (node (ref "R192") (pin "1") (pinfunction "1_1") (pintype "passive"))
    )
    (net (code "128") (name "Net-(Q50-B)") (class "Default")
      (node (ref "Q50") (pin "1") (pinfunction "B_1") (pintype "passive"))
      (node (ref "R181") (pin "2") (pinfunction "2_2") (pintype "passive"))
    )
    (net (code "129") (name "Net-(Q50-C)") (class "Default")
      (node (ref "Q50") (pin "3") (pinfunction "C_3") (pintype "passive"))
      (node (ref "R187") (pin "1") (pinfunction "1_1") (pintype "passive"))
      (node (ref "R193") (pin "1") (pinfunction "1_1") (pintype "passive"))
    )
    (net (code "130") (name "Net-(Q51-B)") (class "Default")
      (node (ref "Q51") (pin "1") (pinfunction "B_1") (pintype "passive"))
      (node (ref "R182") (pin "2") (pinfunction "2_2") (pintype "passive"))
    )
    (net (code "131") (name "Net-(Q51-C)") (class "Default")
      (node (ref "Q51") (pin "3") (pinfunction "C_3") (pintype "passive"))
      (node (ref "R188") (pin "1") (pinfunction "1_1") (pintype "passive"))
      (node (ref "R194") (pin "1") (pinfunction "1_1") (pintype "passive"))
    )
    (net (code "132") (name "Net-(Q55-B)") (class "Default")
      (node (ref "Q55") (pin "1") (pinfunction "B_1") (pintype "passive"))
      (node (ref "R198") (pin "2") (pinfunction "2_2") (pintype "passive"))
    )
    (net (code "133") (name "Net-(Q55-C)") (class "Default")
      (node (ref "Q55") (pin "3") (pinfunction "C_3") (pintype "passive"))
      (node (ref "R204") (pin "1") (pinfunction "1_1") (pintype "passive"))
      (node (ref "R210") (pin "1") (pinfunction "1_1") (pintype "passive"))
    )
    (net (code "134") (name "Net-(Q56-B)") (class "Default")
      (node (ref "Q56") (pin "1") (pinfunction "B_1") (pintype "passive"))
      (node (ref "R199") (pin "2") (pinfunction "2_2") (pintype "passive"))
    )
    (net (code "135") (name "Net-(Q56-C)") (class "Default")
      (node (ref "Q56") (pin "3") (pinfunction "C_3") (pintype "passive"))
      (node (ref "R205") (pin "1") (pinfunction "1_1") (pintype "passive"))
      (node (ref "R211") (pin "1") (pinfunction "1_1") (pintype "passive"))
    )
    (net (code "136") (name "Net-(Q57-B)") (class "Default")
      (node (ref "Q57") (pin "1") (pinfunction "B_1") (pintype "passive"))
      (node (ref "R200") (pin "2") (pinfunction "2_2") (pintype "passive"))
    )
    (net (code "137") (name "Net-(Q57-C)") (class "Default")
      (node (ref "Q57") (pin "3") (pinfunction "C_3") (pintype "passive"))
      (node (ref "R206") (pin "1") (pinfunction "1_1") (pintype "passive"))
      (node (ref "R212") (pin "1") (pinfunction "1_1") (pintype "passive"))
    )
    (net (code "138") (name "Net-(Q61-B)") (class "Default")
      (node (ref "Q61") (pin "1") (pinfunction "B_1") (pintype "passive"))
      (node (ref "R216") (pin "2") (pinfunction "2_2") (pintype "passive"))
    )
    (net (code "139") (name "Net-(Q61-C)") (class "Default")
      (node (ref "Q61") (pin "3") (pinfunction "C_3") (pintype "passive"))
      (node (ref "R222") (pin "1") (pinfunction "1_1") (pintype "passive"))
      (node (ref "R228") (pin "1") (pinfunction "1_1") (pintype "passive"))
    )
    (net (code "140") (name "Net-(Q62-B)") (class "Default")
      (node (ref "Q62") (pin "1") (pinfunction "B_1") (pintype "passive"))
      (node (ref "R217") (pin "2") (pinfunction "2_2") (pintype "passive"))
    )
    (net (code "141") (name "Net-(Q62-C)") (class "Default")
      (node (ref "Q62") (pin "3") (pinfunction "C_3") (pintype "passive"))
      (node (ref "R223") (pin "1") (pinfunction "1_1") (pintype "passive"))
      (node (ref "R229") (pin "1") (pinfunction "1_1") (pintype "passive"))
    )
    (net (code "142") (name "Net-(Q63-B)") (class "Default")
      (node (ref "Q63") (pin "1") (pinfunction "B_1") (pintype "passive"))
      (node (ref "R218") (pin "2") (pinfunction "2_2") (pintype "passive"))
    )
    (net (code "143") (name "Net-(Q63-C)") (class "Default")
      (node (ref "Q63") (pin "3") (pinfunction "C_3") (pintype "passive"))
      (node (ref "R224") (pin "1") (pinfunction "1_1") (pintype "passive"))
      (node (ref "R230") (pin "1") (pinfunction "1_1") (pintype "passive"))
    )
    (net (code "144") (name "Net-(U22-Q1)") (class "Default")
      (node (ref "R108") (pin "1") (pinfunction "1_1") (pintype "passive"))
      (node (ref "U22") (pin "19") (pinfunction "Q1_19") (pintype "tri_state"))
    )
    (net (code "145") (name "Net-(U22-Q2)") (class "Default")
      (node (ref "R126") (pin "1") (pinfunction "1_1") (pintype "passive"))
      (node (ref "U22") (pin "18") (pinfunction "Q2_18") (pintype "tri_state"))
    )
    (net (code "146") (name "Net-(U22-Q3)") (class "Default")
      (node (ref "R144") (pin "1") (pinfunction "1_1") (pintype "passive"))
      (node (ref "U22") (pin "17") (pinfunction "Q3_17") (pintype "tri_state"))
    )
    (net (code "147") (name "Net-(U22-Q4)") (class "Default")
      (node (ref "R162") (pin "1") (pinfunction "1_1") (pintype "passive"))
      (node (ref "U22") (pin "16") (pinfunction "Q4_16") (pintype "tri_state"))
    )
    (net (code "148") (name "Net-(U22-Q5)") (class "Default")
      (node (ref "R180") (pin "1") (pinfunction "1_1") (pintype "passive"))
      (node (ref "U22") (pin "15") (pinfunction "Q5_15") (pintype "tri_state"))
    )
    (net (code "149") (name "Net-(U22-Q6)") (class "Default")
      (node (ref "R198") (pin "1") (pinfunction "1_1") (pintype "passive"))
      (node (ref "U22") (pin "14") (pinfunction "Q6_14") (pintype "tri_state"))
    )
    (net (code "150") (name "Net-(U22-Q7)") (class "Default")
      (node (ref "R216") (pin "1") (pinfunction "1_1") (pintype "passive"))
      (node (ref "U22") (pin "13") (pinfunction "Q7_13") (pintype "tri_state"))
    )
    (net (code "151") (name "Net-(U23-Q1)") (class "Default")
      (node (ref "R109") (pin "1") (pinfunction "1_1") (pintype "passive"))
      (node (ref "U23") (pin "19") (pinfunction "Q1_19") (pintype "tri_state"))
    )
    (net (code "152") (name "Net-(U23-Q2)") (class "Default")
      (node (ref "R127") (pin "1") (pinfunction "1_1") (pintype "passive"))
      (node (ref "U23") (pin "18") (pinfunction "Q2_18") (pintype "tri_state"))
    )
    (net (code "153") (name "Net-(U23-Q3)") (class "Default")
      (node (ref "R145") (pin "1") (pinfunction "1_1") (pintype "passive"))
      (node (ref "U23") (pin "17") (pinfunction "Q3_17") (pintype "tri_state"))
    )
    (net (code "154") (name "Net-(U23-Q4)") (class "Default")
      (node (ref "R163") (pin "1") (pinfunction "1_1") (pintype "passive"))
      (node (ref "U23") (pin "16") (pinfunction "Q4_16") (pintype "tri_state"))
    )
    (net (code "155") (name "Net-(U23-Q5)") (class "Default")
      (node (ref "R181") (pin "1") (pinfunction "1_1") (pintype "passive"))
      (node (ref "U23") (pin "15") (pinfunction "Q5_15") (pintype "tri_state"))
    )
    (net (code "156") (name "Net-(U23-Q6)") (class "Default")
      (node (ref "R199") (pin "1") (pinfunction "1_1") (pintype "passive"))
      (node (ref "U23") (pin "14") (pinfunction "Q6_14") (pintype "tri_state"))
    )
    (net (code "157") (name "Net-(U23-Q7)") (class "Default")
      (node (ref "R217") (pin "1") (pinfunction "1_1") (pintype "passive"))
      (node (ref "U23") (pin "13") (pinfunction "Q7_13") (pintype "tri_state"))
    )
    (net (code "158") (name "Net-(U24-Q1)") (class "Default")
      (node (ref "R110") (pin "1") (pinfunction "1_1") (pintype "passive"))
      (node (ref "U24") (pin "19") (pinfunction "Q1_19") (pintype "tri_state"))
    )
    (net (code "159") (name "Net-(U24-Q2)") (class "Default")
      (node (ref "R128") (pin "1") (pinfunction "1_1") (pintype "passive"))
      (node (ref "U24") (pin "18") (pinfunction "Q2_18") (pintype "tri_state"))
    )
    (net (code "160") (name "Net-(U24-Q3)") (class "Default")
      (node (ref "R146") (pin "1") (pinfunction "1_1") (pintype "passive"))
      (node (ref "U24") (pin "17") (pinfunction "Q3_17") (pintype "tri_state"))
    )
    (net (code "161") (name "Net-(U24-Q4)") (class "Default")
      (node (ref "R164") (pin "1") (pinfunction "1_1") (pintype "passive"))
      (node (ref "U24") (pin "16") (pinfunction "Q4_16") (pintype "tri_state"))
    )
    (net (code "162") (name "Net-(U24-Q5)") (class "Default")
      (node (ref "R182") (pin "1") (pinfunction "1_1") (pintype "passive"))
      (node (ref "U24") (pin "15") (pinfunction "Q5_15") (pintype "tri_state"))
    )
    (net (code "163") (name "Net-(U24-Q6)") (class "Default")
      (node (ref "R200") (pin "1") (pinfunction "1_1") (pintype "passive"))
      (node (ref "U24") (pin "14") (pinfunction "Q6_14") (pintype "tri_state"))
    )
    (net (code "164") (name "Net-(U24-Q7)") (class "Default")
      (node (ref "R218") (pin "1") (pinfunction "1_1") (pintype "passive"))
      (node (ref "U24") (pin "13") (pinfunction "Q7_13") (pintype "tri_state"))
    )
    (net (code "165") (name "VCC") (class "Default")
      (node (ref "C50") (pin "1") (pinfunction "1_1") (pintype "passive"))
      (node (ref "C51") (pin "1") (pinfunction "1_1") (pintype "passive"))
      (node (ref "C52") (pin "1") (pinfunction "1_1") (pintype "passive"))
      (node (ref "U22") (pin "20") (pinfunction "VCC_20") (pintype "power_in"))
      (node (ref "U23") (pin "20") (pinfunction "VCC_20") (pintype "power_in"))
      (node (ref "U24") (pin "20") (pinfunction "VCC_20") (pintype "power_in"))
    )
  )
)
